# Insole_ver1_chi.net
KiCad netlist of a schematic drawn in Altium Designer
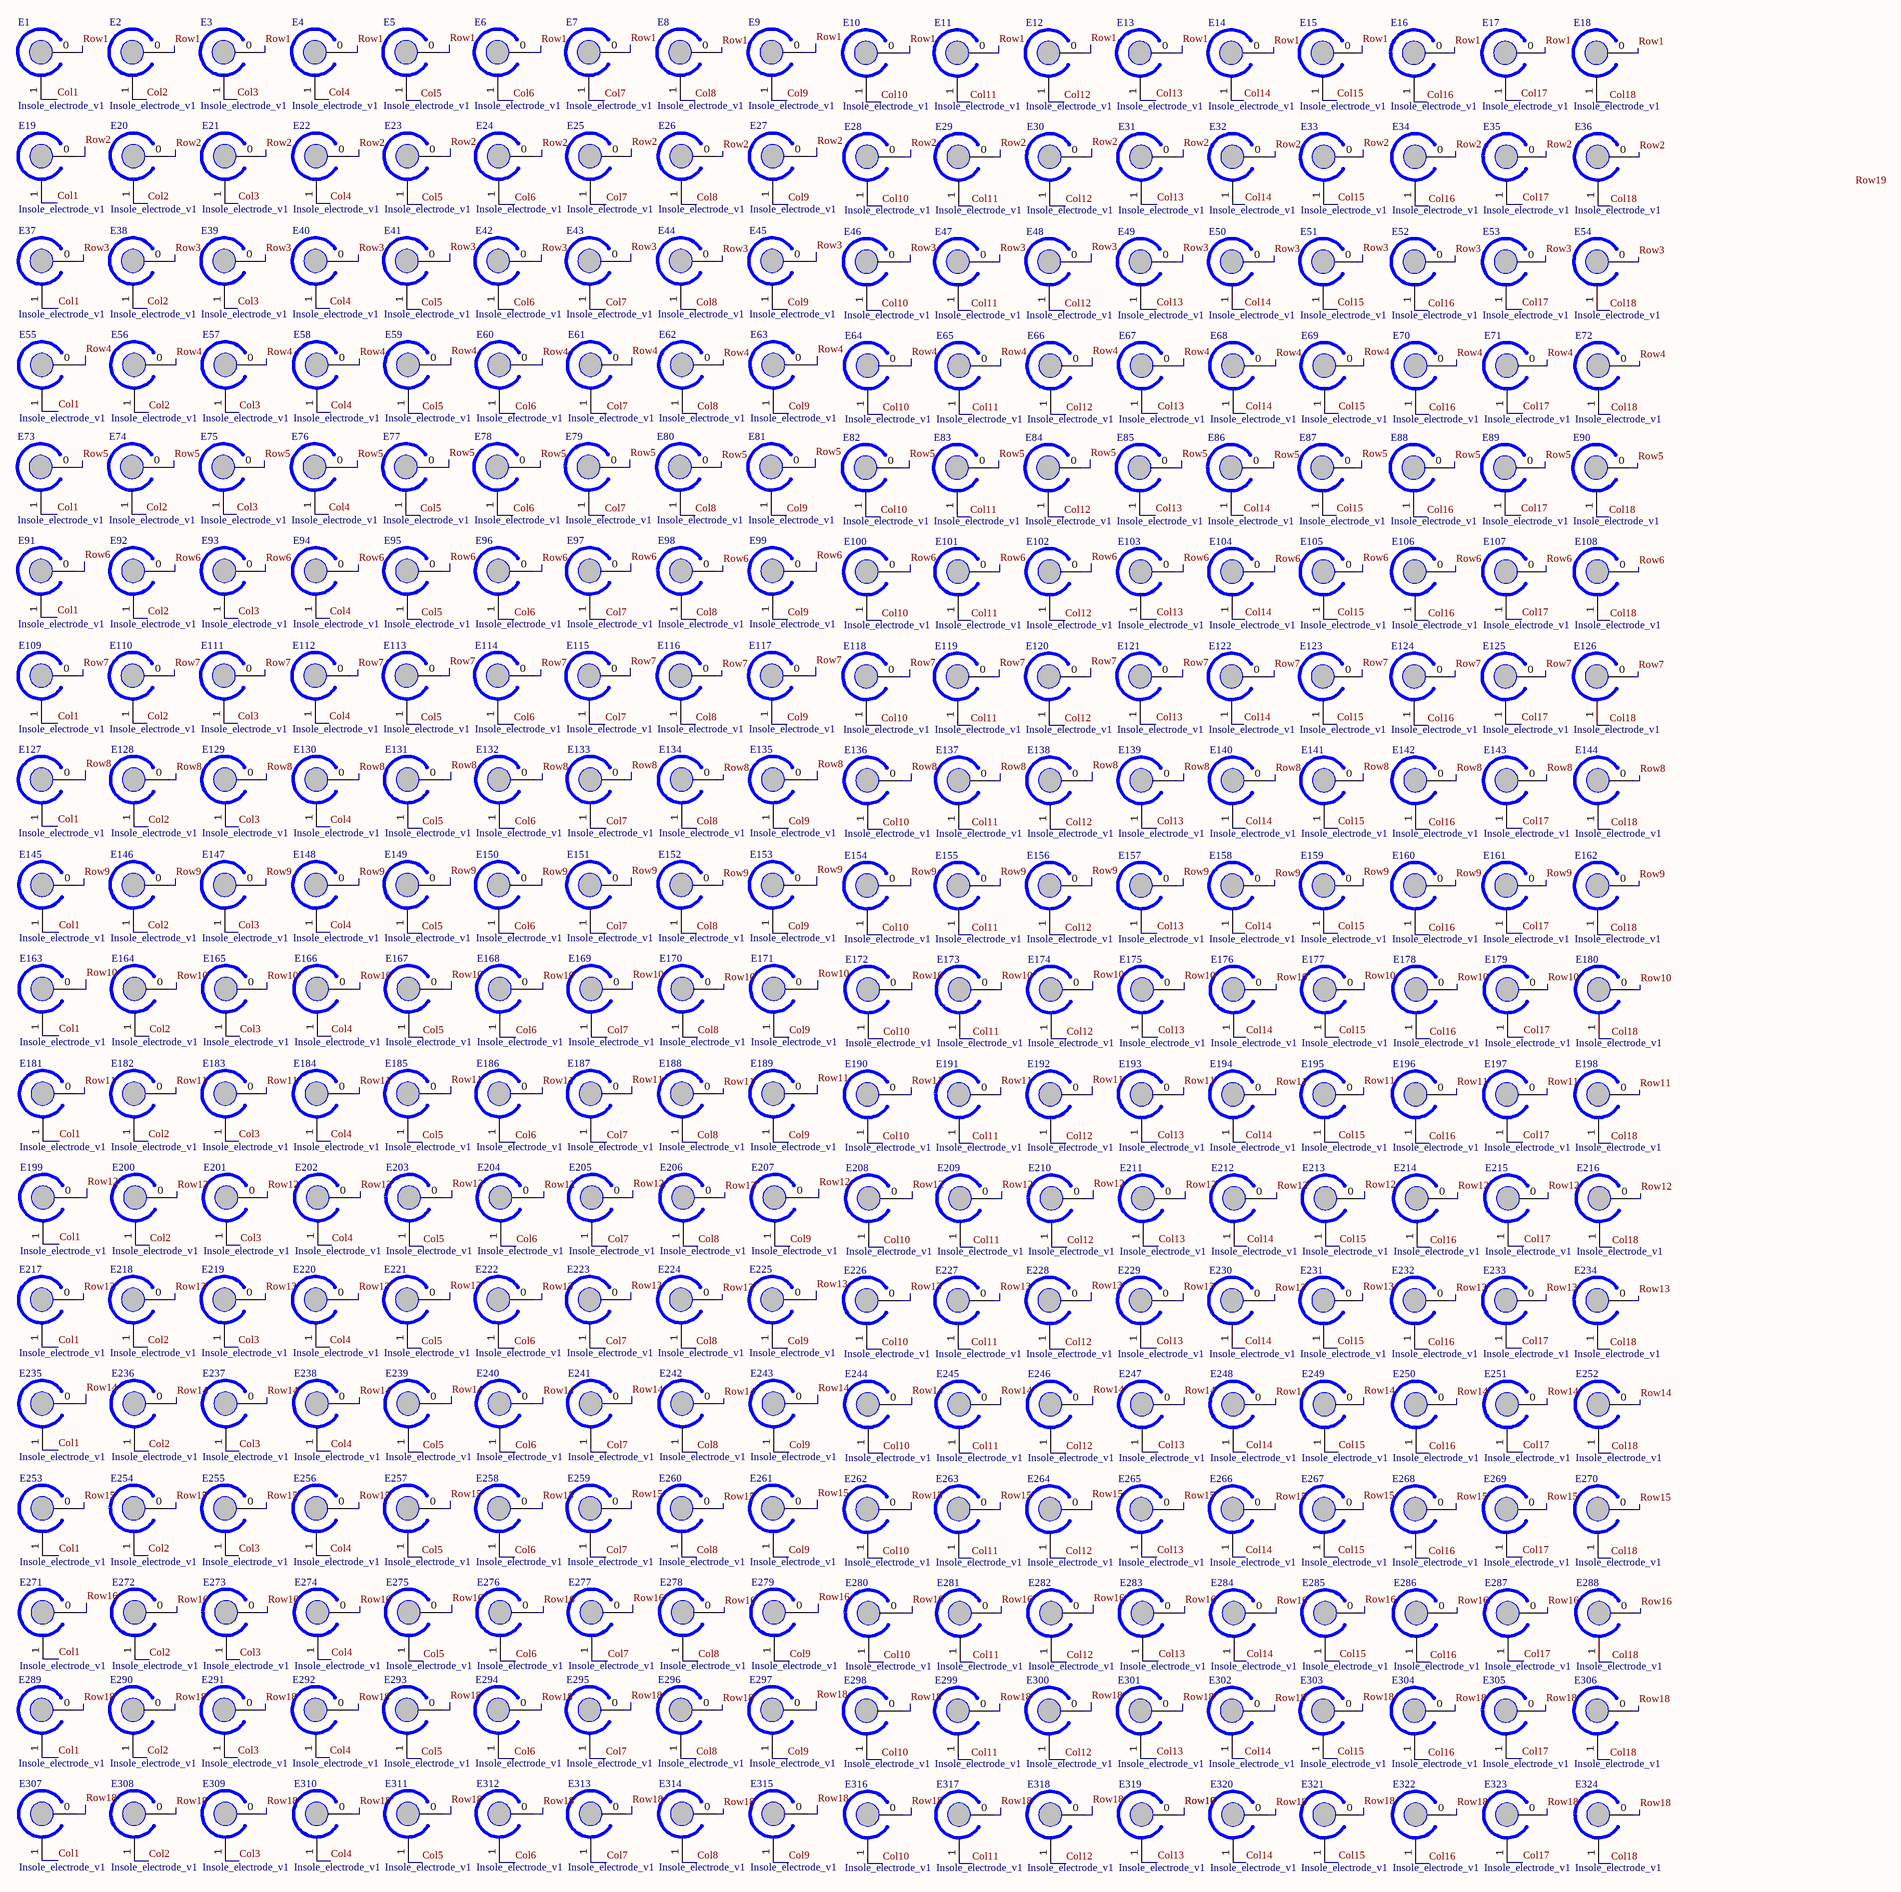
[diagram p0: Insole_ver1_chi.SchDoc]

(export (version "E")
  (design (tool "Eeschema 10.0.6"))
  (components
    (comp (ref "E1")
      (value "Insole_electrode_v1")
      (footprint "insole_electrode_v1")
      (libsource (lib "UCL") (part "Insole_electrode_v1"))
    )
    (comp (ref "E2")
      (value "Insole_electrode_v1")
      (footprint "insole_electrode_v1")
      (libsource (lib "UCL") (part "Insole_electrode_v1"))
    )
    (comp (ref "E3")
      (value "Insole_electrode_v1")
      (footprint "insole_electrode_v1")
      (libsource (lib "UCL") (part "Insole_electrode_v1"))
    )
    (comp (ref "E4")
      (value "Insole_electrode_v1")
      (footprint "insole_electrode_v1")
      (libsource (lib "UCL") (part "Insole_electrode_v1"))
    )
    (comp (ref "E5")
      (value "Insole_electrode_v1")
      (footprint "insole_electrode_v1")
      (libsource (lib "UCL") (part "Insole_electrode_v1"))
    )
    (comp (ref "E6")
      (value "Insole_electrode_v1")
      (footprint "insole_electrode_v1")
      (libsource (lib "UCL") (part "Insole_electrode_v1"))
    )
    (comp (ref "E7")
      (value "Insole_electrode_v1")
      (footprint "insole_electrode_v1")
      (libsource (lib "UCL") (part "Insole_electrode_v1"))
    )
    (comp (ref "E8")
      (value "Insole_electrode_v1")
      (footprint "insole_electrode_v1")
      (libsource (lib "UCL") (part "Insole_electrode_v1"))
    )
    (comp (ref "E9")
      (value "Insole_electrode_v1")
      (footprint "insole_electrode_v1")
      (libsource (lib "UCL") (part "Insole_electrode_v1"))
    )
    (comp (ref "E10")
      (value "Insole_electrode_v1")
      (footprint "insole_electrode_v1")
      (libsource (lib "UCL") (part "Insole_electrode_v1"))
    )
    (comp (ref "E11")
      (value "Insole_electrode_v1")
      (footprint "insole_electrode_v1")
      (libsource (lib "UCL") (part "Insole_electrode_v1"))
    )
    (comp (ref "E12")
      (value "Insole_electrode_v1")
      (footprint "insole_electrode_v1")
      (libsource (lib "UCL") (part "Insole_electrode_v1"))
    )
    (comp (ref "E13")
      (value "Insole_electrode_v1")
      (footprint "insole_electrode_v1")
      (libsource (lib "UCL") (part "Insole_electrode_v1"))
    )
    (comp (ref "E14")
      (value "Insole_electrode_v1")
      (footprint "insole_electrode_v1")
      (libsource (lib "UCL") (part "Insole_electrode_v1"))
    )
    (comp (ref "E15")
      (value "Insole_electrode_v1")
      (footprint "insole_electrode_v1")
      (libsource (lib "UCL") (part "Insole_electrode_v1"))
    )
    (comp (ref "E16")
      (value "Insole_electrode_v1")
      (footprint "insole_electrode_v1")
      (libsource (lib "UCL") (part "Insole_electrode_v1"))
    )
    (comp (ref "E17")
      (value "Insole_electrode_v1")
      (footprint "insole_electrode_v1")
      (libsource (lib "UCL") (part "Insole_electrode_v1"))
    )
    (comp (ref "E18")
      (value "Insole_electrode_v1")
      (footprint "insole_electrode_v1")
      (libsource (lib "UCL") (part "Insole_electrode_v1"))
    )
    (comp (ref "E19")
      (value "Insole_electrode_v1")
      (footprint "insole_electrode_v1")
      (libsource (lib "UCL") (part "Insole_electrode_v1"))
    )
    (comp (ref "E20")
      (value "Insole_electrode_v1")
      (footprint "insole_electrode_v1")
      (libsource (lib "UCL") (part "Insole_electrode_v1"))
    )
    (comp (ref "E21")
      (value "Insole_electrode_v1")
      (footprint "insole_electrode_v1")
      (libsource (lib "UCL") (part "Insole_electrode_v1"))
    )
    (comp (ref "E22")
      (value "Insole_electrode_v1")
      (footprint "insole_electrode_v1")
      (libsource (lib "UCL") (part "Insole_electrode_v1"))
    )
    (comp (ref "E23")
      (value "Insole_electrode_v1")
      (footprint "insole_electrode_v1")
      (libsource (lib "UCL") (part "Insole_electrode_v1"))
    )
    (comp (ref "E24")
      (value "Insole_electrode_v1")
      (footprint "insole_electrode_v1")
      (libsource (lib "UCL") (part "Insole_electrode_v1"))
    )
    (comp (ref "E25")
      (value "Insole_electrode_v1")
      (footprint "insole_electrode_v1")
      (libsource (lib "UCL") (part "Insole_electrode_v1"))
    )
    (comp (ref "E26")
      (value "Insole_electrode_v1")
      (footprint "insole_electrode_v1")
      (libsource (lib "UCL") (part "Insole_electrode_v1"))
    )
    (comp (ref "E27")
      (value "Insole_electrode_v1")
      (footprint "insole_electrode_v1")
      (libsource (lib "UCL") (part "Insole_electrode_v1"))
    )
    (comp (ref "E28")
      (value "Insole_electrode_v1")
      (footprint "insole_electrode_v1")
      (libsource (lib "UCL") (part "Insole_electrode_v1"))
    )
    (comp (ref "E29")
      (value "Insole_electrode_v1")
      (footprint "insole_electrode_v1")
      (libsource (lib "UCL") (part "Insole_electrode_v1"))
    )
    (comp (ref "E30")
      (value "Insole_electrode_v1")
      (footprint "insole_electrode_v1")
      (libsource (lib "UCL") (part "Insole_electrode_v1"))
    )
    (comp (ref "E31")
      (value "Insole_electrode_v1")
      (footprint "insole_electrode_v1")
      (libsource (lib "UCL") (part "Insole_electrode_v1"))
    )
    (comp (ref "E32")
      (value "Insole_electrode_v1")
      (footprint "insole_electrode_v1")
      (libsource (lib "UCL") (part "Insole_electrode_v1"))
    )
    (comp (ref "E33")
      (value "Insole_electrode_v1")
      (footprint "insole_electrode_v1")
      (libsource (lib "UCL") (part "Insole_electrode_v1"))
    )
    (comp (ref "E34")
      (value "Insole_electrode_v1")
      (footprint "insole_electrode_v1")
      (libsource (lib "UCL") (part "Insole_electrode_v1"))
    )
    (comp (ref "E35")
      (value "Insole_electrode_v1")
      (footprint "insole_electrode_v1")
      (libsource (lib "UCL") (part "Insole_electrode_v1"))
    )
    (comp (ref "E36")
      (value "Insole_electrode_v1")
      (footprint "insole_electrode_v1")
      (libsource (lib "UCL") (part "Insole_electrode_v1"))
    )
    (comp (ref "E37")
      (value "Insole_electrode_v1")
      (footprint "insole_electrode_v1")
      (libsource (lib "UCL") (part "Insole_electrode_v1"))
    )
    (comp (ref "E38")
      (value "Insole_electrode_v1")
      (footprint "insole_electrode_v1")
      (libsource (lib "UCL") (part "Insole_electrode_v1"))
    )
    (comp (ref "E39")
      (value "Insole_electrode_v1")
      (footprint "insole_electrode_v1")
      (libsource (lib "UCL") (part "Insole_electrode_v1"))
    )
    (comp (ref "E40")
      (value "Insole_electrode_v1")
      (footprint "insole_electrode_v1")
      (libsource (lib "UCL") (part "Insole_electrode_v1"))
    )
    (comp (ref "E41")
      (value "Insole_electrode_v1")
      (footprint "insole_electrode_v1")
      (libsource (lib "UCL") (part "Insole_electrode_v1"))
    )
    (comp (ref "E42")
      (value "Insole_electrode_v1")
      (footprint "insole_electrode_v1")
      (libsource (lib "UCL") (part "Insole_electrode_v1"))
    )
    (comp (ref "E43")
      (value "Insole_electrode_v1")
      (footprint "insole_electrode_v1")
      (libsource (lib "UCL") (part "Insole_electrode_v1"))
    )
    (comp (ref "E44")
      (value "Insole_electrode_v1")
      (footprint "insole_electrode_v1")
      (libsource (lib "UCL") (part "Insole_electrode_v1"))
    )
    (comp (ref "E45")
      (value "Insole_electrode_v1")
      (footprint "insole_electrode_v1")
      (libsource (lib "UCL") (part "Insole_electrode_v1"))
    )
    (comp (ref "E46")
      (value "Insole_electrode_v1")
      (footprint "insole_electrode_v1")
      (libsource (lib "UCL") (part "Insole_electrode_v1"))
    )
    (comp (ref "E47")
      (value "Insole_electrode_v1")
      (footprint "insole_electrode_v1")
      (libsource (lib "UCL") (part "Insole_electrode_v1"))
    )
    (comp (ref "E48")
      (value "Insole_electrode_v1")
      (footprint "insole_electrode_v1")
      (libsource (lib "UCL") (part "Insole_electrode_v1"))
    )
    (comp (ref "E49")
      (value "Insole_electrode_v1")
      (footprint "insole_electrode_v1")
      (libsource (lib "UCL") (part "Insole_electrode_v1"))
    )
    (comp (ref "E50")
      (value "Insole_electrode_v1")
      (footprint "insole_electrode_v1")
      (libsource (lib "UCL") (part "Insole_electrode_v1"))
    )
    (comp (ref "E51")
      (value "Insole_electrode_v1")
      (footprint "insole_electrode_v1")
      (libsource (lib "UCL") (part "Insole_electrode_v1"))
    )
    (comp (ref "E52")
      (value "Insole_electrode_v1")
      (footprint "insole_electrode_v1")
      (libsource (lib "UCL") (part "Insole_electrode_v1"))
    )
    (comp (ref "E53")
      (value "Insole_electrode_v1")
      (footprint "insole_electrode_v1")
      (libsource (lib "UCL") (part "Insole_electrode_v1"))
    )
    (comp (ref "E54")
      (value "Insole_electrode_v1")
      (footprint "insole_electrode_v1")
      (libsource (lib "UCL") (part "Insole_electrode_v1"))
    )
    (comp (ref "E55")
      (value "Insole_electrode_v1")
      (footprint "insole_electrode_v1")
      (libsource (lib "UCL") (part "Insole_electrode_v1"))
    )
    (comp (ref "E56")
      (value "Insole_electrode_v1")
      (footprint "insole_electrode_v1")
      (libsource (lib "UCL") (part "Insole_electrode_v1"))
    )
    (comp (ref "E57")
      (value "Insole_electrode_v1")
      (footprint "insole_electrode_v1")
      (libsource (lib "UCL") (part "Insole_electrode_v1"))
    )
    (comp (ref "E58")
      (value "Insole_electrode_v1")
      (footprint "insole_electrode_v1")
      (libsource (lib "UCL") (part "Insole_electrode_v1"))
    )
    (comp (ref "E59")
      (value "Insole_electrode_v1")
      (footprint "insole_electrode_v1")
      (libsource (lib "UCL") (part "Insole_electrode_v1"))
    )
    (comp (ref "E60")
      (value "Insole_electrode_v1")
      (footprint "insole_electrode_v1")
      (libsource (lib "UCL") (part "Insole_electrode_v1"))
    )
    (comp (ref "E61")
      (value "Insole_electrode_v1")
      (footprint "insole_electrode_v1")
      (libsource (lib "UCL") (part "Insole_electrode_v1"))
    )
    (comp (ref "E62")
      (value "Insole_electrode_v1")
      (footprint "insole_electrode_v1")
      (libsource (lib "UCL") (part "Insole_electrode_v1"))
    )
    (comp (ref "E63")
      (value "Insole_electrode_v1")
      (footprint "insole_electrode_v1")
      (libsource (lib "UCL") (part "Insole_electrode_v1"))
    )
    (comp (ref "E64")
      (value "Insole_electrode_v1")
      (footprint "insole_electrode_v1")
      (libsource (lib "UCL") (part "Insole_electrode_v1"))
    )
    (comp (ref "E65")
      (value "Insole_electrode_v1")
      (footprint "insole_electrode_v1")
      (libsource (lib "UCL") (part "Insole_electrode_v1"))
    )
    (comp (ref "E66")
      (value "Insole_electrode_v1")
      (footprint "insole_electrode_v1")
      (libsource (lib "UCL") (part "Insole_electrode_v1"))
    )
    (comp (ref "E67")
      (value "Insole_electrode_v1")
      (footprint "insole_electrode_v1")
      (libsource (lib "UCL") (part "Insole_electrode_v1"))
    )
    (comp (ref "E68")
      (value "Insole_electrode_v1")
      (footprint "insole_electrode_v1")
      (libsource (lib "UCL") (part "Insole_electrode_v1"))
    )
    (comp (ref "E69")
      (value "Insole_electrode_v1")
      (footprint "insole_electrode_v1")
      (libsource (lib "UCL") (part "Insole_electrode_v1"))
    )
    (comp (ref "E70")
      (value "Insole_electrode_v1")
      (footprint "insole_electrode_v1")
      (libsource (lib "UCL") (part "Insole_electrode_v1"))
    )
    (comp (ref "E71")
      (value "Insole_electrode_v1")
      (footprint "insole_electrode_v1")
      (libsource (lib "UCL") (part "Insole_electrode_v1"))
    )
    (comp (ref "E72")
      (value "Insole_electrode_v1")
      (footprint "insole_electrode_v1")
      (libsource (lib "UCL") (part "Insole_electrode_v1"))
    )
    (comp (ref "E73")
      (value "Insole_electrode_v1")
      (footprint "insole_electrode_v1")
      (libsource (lib "UCL") (part "Insole_electrode_v1"))
    )
    (comp (ref "E74")
      (value "Insole_electrode_v1")
      (footprint "insole_electrode_v1")
      (libsource (lib "UCL") (part "Insole_electrode_v1"))
    )
    (comp (ref "E75")
      (value "Insole_electrode_v1")
      (footprint "insole_electrode_v1")
      (libsource (lib "UCL") (part "Insole_electrode_v1"))
    )
    (comp (ref "E76")
      (value "Insole_electrode_v1")
      (footprint "insole_electrode_v1")
      (libsource (lib "UCL") (part "Insole_electrode_v1"))
    )
    (comp (ref "E77")
      (value "Insole_electrode_v1")
      (footprint "insole_electrode_v1")
      (libsource (lib "UCL") (part "Insole_electrode_v1"))
    )
    (comp (ref "E78")
      (value "Insole_electrode_v1")
      (footprint "insole_electrode_v1")
      (libsource (lib "UCL") (part "Insole_electrode_v1"))
    )
    (comp (ref "E79")
      (value "Insole_electrode_v1")
      (footprint "insole_electrode_v1")
      (libsource (lib "UCL") (part "Insole_electrode_v1"))
    )
    (comp (ref "E80")
      (value "Insole_electrode_v1")
      (footprint "insole_electrode_v1")
      (libsource (lib "UCL") (part "Insole_electrode_v1"))
    )
    (comp (ref "E81")
      (value "Insole_electrode_v1")
      (footprint "insole_electrode_v1")
      (libsource (lib "UCL") (part "Insole_electrode_v1"))
    )
    (comp (ref "E82")
      (value "Insole_electrode_v1")
      (footprint "insole_electrode_v1")
      (libsource (lib "UCL") (part "Insole_electrode_v1"))
    )
    (comp (ref "E83")
      (value "Insole_electrode_v1")
      (footprint "insole_electrode_v1")
      (libsource (lib "UCL") (part "Insole_electrode_v1"))
    )
    (comp (ref "E84")
      (value "Insole_electrode_v1")
      (footprint "insole_electrode_v1")
      (libsource (lib "UCL") (part "Insole_electrode_v1"))
    )
    (comp (ref "E85")
      (value "Insole_electrode_v1")
      (footprint "insole_electrode_v1")
      (libsource (lib "UCL") (part "Insole_electrode_v1"))
    )
    (comp (ref "E86")
      (value "Insole_electrode_v1")
      (footprint "insole_electrode_v1")
      (libsource (lib "UCL") (part "Insole_electrode_v1"))
    )
    (comp (ref "E87")
      (value "Insole_electrode_v1")
      (footprint "insole_electrode_v1")
      (libsource (lib "UCL") (part "Insole_electrode_v1"))
    )
    (comp (ref "E88")
      (value "Insole_electrode_v1")
      (footprint "insole_electrode_v1")
      (libsource (lib "UCL") (part "Insole_electrode_v1"))
    )
    (comp (ref "E89")
      (value "Insole_electrode_v1")
      (footprint "insole_electrode_v1")
      (libsource (lib "UCL") (part "Insole_electrode_v1"))
    )
    (comp (ref "E90")
      (value "Insole_electrode_v1")
      (footprint "insole_electrode_v1")
      (libsource (lib "UCL") (part "Insole_electrode_v1"))
    )
    (comp (ref "E91")
      (value "Insole_electrode_v1")
      (footprint "insole_electrode_v1")
      (libsource (lib "UCL") (part "Insole_electrode_v1"))
    )
    (comp (ref "E92")
      (value "Insole_electrode_v1")
      (footprint "insole_electrode_v1")
      (libsource (lib "UCL") (part "Insole_electrode_v1"))
    )
    (comp (ref "E93")
      (value "Insole_electrode_v1")
      (footprint "insole_electrode_v1")
      (libsource (lib "UCL") (part "Insole_electrode_v1"))
    )
    (comp (ref "E94")
      (value "Insole_electrode_v1")
      (footprint "insole_electrode_v1")
      (libsource (lib "UCL") (part "Insole_electrode_v1"))
    )
    (comp (ref "E95")
      (value "Insole_electrode_v1")
      (footprint "insole_electrode_v1")
      (libsource (lib "UCL") (part "Insole_electrode_v1"))
    )
    (comp (ref "E96")
      (value "Insole_electrode_v1")
      (footprint "insole_electrode_v1")
      (libsource (lib "UCL") (part "Insole_electrode_v1"))
    )
    (comp (ref "E97")
      (value "Insole_electrode_v1")
      (footprint "insole_electrode_v1")
      (libsource (lib "UCL") (part "Insole_electrode_v1"))
    )
    (comp (ref "E98")
      (value "Insole_electrode_v1")
      (footprint "insole_electrode_v1")
      (libsource (lib "UCL") (part "Insole_electrode_v1"))
    )
    (comp (ref "E99")
      (value "Insole_electrode_v1")
      (footprint "insole_electrode_v1")
      (libsource (lib "UCL") (part "Insole_electrode_v1"))
    )
    (comp (ref "E100")
      (value "Insole_electrode_v1")
      (footprint "insole_electrode_v1")
      (libsource (lib "UCL") (part "Insole_electrode_v1"))
    )
    (comp (ref "E101")
      (value "Insole_electrode_v1")
      (footprint "insole_electrode_v1")
      (libsource (lib "UCL") (part "Insole_electrode_v1"))
    )
    (comp (ref "E102")
      (value "Insole_electrode_v1")
      (footprint "insole_electrode_v1")
      (libsource (lib "UCL") (part "Insole_electrode_v1"))
    )
    (comp (ref "E103")
      (value "Insole_electrode_v1")
      (footprint "insole_electrode_v1")
      (libsource (lib "UCL") (part "Insole_electrode_v1"))
    )
    (comp (ref "E104")
      (value "Insole_electrode_v1")
      (footprint "insole_electrode_v1")
      (libsource (lib "UCL") (part "Insole_electrode_v1"))
    )
    (comp (ref "E105")
      (value "Insole_electrode_v1")
      (footprint "insole_electrode_v1")
      (libsource (lib "UCL") (part "Insole_electrode_v1"))
    )
    (comp (ref "E106")
      (value "Insole_electrode_v1")
      (footprint "insole_electrode_v1")
      (libsource (lib "UCL") (part "Insole_electrode_v1"))
    )
    (comp (ref "E107")
      (value "Insole_electrode_v1")
      (footprint "insole_electrode_v1")
      (libsource (lib "UCL") (part "Insole_electrode_v1"))
    )
    (comp (ref "E108")
      (value "Insole_electrode_v1")
      (footprint "insole_electrode_v1")
      (libsource (lib "UCL") (part "Insole_electrode_v1"))
    )
    (comp (ref "E109")
      (value "Insole_electrode_v1")
      (footprint "insole_electrode_v1")
      (libsource (lib "UCL") (part "Insole_electrode_v1"))
    )
    (comp (ref "E110")
      (value "Insole_electrode_v1")
      (footprint "insole_electrode_v1")
      (libsource (lib "UCL") (part "Insole_electrode_v1"))
    )
    (comp (ref "E111")
      (value "Insole_electrode_v1")
      (footprint "insole_electrode_v1")
      (libsource (lib "UCL") (part "Insole_electrode_v1"))
    )
    (comp (ref "E112")
      (value "Insole_electrode_v1")
      (footprint "insole_electrode_v1")
      (libsource (lib "UCL") (part "Insole_electrode_v1"))
    )
    (comp (ref "E113")
      (value "Insole_electrode_v1")
      (footprint "insole_electrode_v1")
      (libsource (lib "UCL") (part "Insole_electrode_v1"))
    )
    (comp (ref "E114")
      (value "Insole_electrode_v1")
      (footprint "insole_electrode_v1")
      (libsource (lib "UCL") (part "Insole_electrode_v1"))
    )
    (comp (ref "E115")
      (value "Insole_electrode_v1")
      (footprint "insole_electrode_v1")
      (libsource (lib "UCL") (part "Insole_electrode_v1"))
    )
    (comp (ref "E116")
      (value "Insole_electrode_v1")
      (footprint "insole_electrode_v1")
      (libsource (lib "UCL") (part "Insole_electrode_v1"))
    )
    (comp (ref "E117")
      (value "Insole_electrode_v1")
      (footprint "insole_electrode_v1")
      (libsource (lib "UCL") (part "Insole_electrode_v1"))
    )
    (comp (ref "E118")
      (value "Insole_electrode_v1")
      (footprint "insole_electrode_v1")
      (libsource (lib "UCL") (part "Insole_electrode_v1"))
    )
    (comp (ref "E119")
      (value "Insole_electrode_v1")
      (footprint "insole_electrode_v1")
      (libsource (lib "UCL") (part "Insole_electrode_v1"))
    )
    (comp (ref "E120")
      (value "Insole_electrode_v1")
      (footprint "insole_electrode_v1")
      (libsource (lib "UCL") (part "Insole_electrode_v1"))
    )
    (comp (ref "E121")
      (value "Insole_electrode_v1")
      (footprint "insole_electrode_v1")
      (libsource (lib "UCL") (part "Insole_electrode_v1"))
    )
    (comp (ref "E122")
      (value "Insole_electrode_v1")
      (footprint "insole_electrode_v1")
      (libsource (lib "UCL") (part "Insole_electrode_v1"))
    )
    (comp (ref "E123")
      (value "Insole_electrode_v1")
      (footprint "insole_electrode_v1")
      (libsource (lib "UCL") (part "Insole_electrode_v1"))
    )
    (comp (ref "E124")
      (value "Insole_electrode_v1")
      (footprint "insole_electrode_v1")
      (libsource (lib "UCL") (part "Insole_electrode_v1"))
    )
    (comp (ref "E125")
      (value "Insole_electrode_v1")
      (footprint "insole_electrode_v1")
      (libsource (lib "UCL") (part "Insole_electrode_v1"))
    )
    (comp (ref "E126")
      (value "Insole_electrode_v1")
      (footprint "insole_electrode_v1")
      (libsource (lib "UCL") (part "Insole_electrode_v1"))
    )
    (comp (ref "E127")
      (value "Insole_electrode_v1")
      (footprint "insole_electrode_v1")
      (libsource (lib "UCL") (part "Insole_electrode_v1"))
    )
    (comp (ref "E128")
      (value "Insole_electrode_v1")
      (footprint "insole_electrode_v1")
      (libsource (lib "UCL") (part "Insole_electrode_v1"))
    )
    (comp (ref "E129")
      (value "Insole_electrode_v1")
      (footprint "insole_electrode_v1")
      (libsource (lib "UCL") (part "Insole_electrode_v1"))
    )
    (comp (ref "E130")
      (value "Insole_electrode_v1")
      (footprint "insole_electrode_v1")
      (libsource (lib "UCL") (part "Insole_electrode_v1"))
    )
    (comp (ref "E131")
      (value "Insole_electrode_v1")
      (footprint "insole_electrode_v1")
      (libsource (lib "UCL") (part "Insole_electrode_v1"))
    )
    (comp (ref "E132")
      (value "Insole_electrode_v1")
      (footprint "insole_electrode_v1")
      (libsource (lib "UCL") (part "Insole_electrode_v1"))
    )
    (comp (ref "E133")
      (value "Insole_electrode_v1")
      (footprint "insole_electrode_v1")
      (libsource (lib "UCL") (part "Insole_electrode_v1"))
    )
    (comp (ref "E134")
      (value "Insole_electrode_v1")
      (footprint "insole_electrode_v1")
      (libsource (lib "UCL") (part "Insole_electrode_v1"))
    )
    (comp (ref "E135")
      (value "Insole_electrode_v1")
      (footprint "insole_electrode_v1")
      (libsource (lib "UCL") (part "Insole_electrode_v1"))
    )
    (comp (ref "E136")
      (value "Insole_electrode_v1")
      (footprint "insole_electrode_v1")
      (libsource (lib "UCL") (part "Insole_electrode_v1"))
    )
    (comp (ref "E137")
      (value "Insole_electrode_v1")
      (footprint "insole_electrode_v1")
      (libsource (lib "UCL") (part "Insole_electrode_v1"))
    )
    (comp (ref "E138")
      (value "Insole_electrode_v1")
      (footprint "insole_electrode_v1")
      (libsource (lib "UCL") (part "Insole_electrode_v1"))
    )
    (comp (ref "E139")
      (value "Insole_electrode_v1")
      (footprint "insole_electrode_v1")
      (libsource (lib "UCL") (part "Insole_electrode_v1"))
    )
    (comp (ref "E140")
      (value "Insole_electrode_v1")
      (footprint "insole_electrode_v1")
      (libsource (lib "UCL") (part "Insole_electrode_v1"))
    )
    (comp (ref "E141")
      (value "Insole_electrode_v1")
      (footprint "insole_electrode_v1")
      (libsource (lib "UCL") (part "Insole_electrode_v1"))
    )
    (comp (ref "E142")
      (value "Insole_electrode_v1")
      (footprint "insole_electrode_v1")
      (libsource (lib "UCL") (part "Insole_electrode_v1"))
    )
    (comp (ref "E143")
      (value "Insole_electrode_v1")
      (footprint "insole_electrode_v1")
      (libsource (lib "UCL") (part "Insole_electrode_v1"))
    )
    (comp (ref "E144")
      (value "Insole_electrode_v1")
      (footprint "insole_electrode_v1")
      (libsource (lib "UCL") (part "Insole_electrode_v1"))
    )
    (comp (ref "E145")
      (value "Insole_electrode_v1")
      (footprint "insole_electrode_v1")
      (libsource (lib "UCL") (part "Insole_electrode_v1"))
    )
    (comp (ref "E146")
      (value "Insole_electrode_v1")
      (footprint "insole_electrode_v1")
      (libsource (lib "UCL") (part "Insole_electrode_v1"))
    )
    (comp (ref "E147")
      (value "Insole_electrode_v1")
      (footprint "insole_electrode_v1")
      (libsource (lib "UCL") (part "Insole_electrode_v1"))
    )
    (comp (ref "E148")
      (value "Insole_electrode_v1")
      (footprint "insole_electrode_v1")
      (libsource (lib "UCL") (part "Insole_electrode_v1"))
    )
    (comp (ref "E149")
      (value "Insole_electrode_v1")
      (footprint "insole_electrode_v1")
      (libsource (lib "UCL") (part "Insole_electrode_v1"))
    )
    (comp (ref "E150")
      (value "Insole_electrode_v1")
      (footprint "insole_electrode_v1")
      (libsource (lib "UCL") (part "Insole_electrode_v1"))
    )
    (comp (ref "E151")
      (value "Insole_electrode_v1")
      (footprint "insole_electrode_v1")
      (libsource (lib "UCL") (part "Insole_electrode_v1"))
    )
    (comp (ref "E152")
      (value "Insole_electrode_v1")
      (footprint "insole_electrode_v1")
      (libsource (lib "UCL") (part "Insole_electrode_v1"))
    )
    (comp (ref "E153")
      (value "Insole_electrode_v1")
      (footprint "insole_electrode_v1")
      (libsource (lib "UCL") (part "Insole_electrode_v1"))
    )
    (comp (ref "E154")
      (value "Insole_electrode_v1")
      (footprint "insole_electrode_v1")
      (libsource (lib "UCL") (part "Insole_electrode_v1"))
    )
    (comp (ref "E155")
      (value "Insole_electrode_v1")
      (footprint "insole_electrode_v1")
      (libsource (lib "UCL") (part "Insole_electrode_v1"))
    )
    (comp (ref "E156")
      (value "Insole_electrode_v1")
      (footprint "insole_electrode_v1")
      (libsource (lib "UCL") (part "Insole_electrode_v1"))
    )
    (comp (ref "E157")
      (value "Insole_electrode_v1")
      (footprint "insole_electrode_v1")
      (libsource (lib "UCL") (part "Insole_electrode_v1"))
    )
    (comp (ref "E158")
      (value "Insole_electrode_v1")
      (footprint "insole_electrode_v1")
      (libsource (lib "UCL") (part "Insole_electrode_v1"))
    )
    (comp (ref "E159")
      (value "Insole_electrode_v1")
      (footprint "insole_electrode_v1")
      (libsource (lib "UCL") (part "Insole_electrode_v1"))
    )
    (comp (ref "E160")
      (value "Insole_electrode_v1")
      (footprint "insole_electrode_v1")
      (libsource (lib "UCL") (part "Insole_electrode_v1"))
    )
    (comp (ref "E161")
      (value "Insole_electrode_v1")
      (footprint "insole_electrode_v1")
      (libsource (lib "UCL") (part "Insole_electrode_v1"))
    )
    (comp (ref "E162")
      (value "Insole_electrode_v1")
      (footprint "insole_electrode_v1")
      (libsource (lib "UCL") (part "Insole_electrode_v1"))
    )
    (comp (ref "E163")
      (value "Insole_electrode_v1")
      (footprint "insole_electrode_v1")
      (libsource (lib "UCL") (part "Insole_electrode_v1"))
    )
    (comp (ref "E164")
      (value "Insole_electrode_v1")
      (footprint "insole_electrode_v1")
      (libsource (lib "UCL") (part "Insole_electrode_v1"))
    )
    (comp (ref "E165")
      (value "Insole_electrode_v1")
      (footprint "insole_electrode_v1")
      (libsource (lib "UCL") (part "Insole_electrode_v1"))
    )
    (comp (ref "E166")
      (value "Insole_electrode_v1")
      (footprint "insole_electrode_v1")
      (libsource (lib "UCL") (part "Insole_electrode_v1"))
    )
    (comp (ref "E167")
      (value "Insole_electrode_v1")
      (footprint "insole_electrode_v1")
      (libsource (lib "UCL") (part "Insole_electrode_v1"))
    )
    (comp (ref "E168")
      (value "Insole_electrode_v1")
      (footprint "insole_electrode_v1")
      (libsource (lib "UCL") (part "Insole_electrode_v1"))
    )
    (comp (ref "E169")
      (value "Insole_electrode_v1")
      (footprint "insole_electrode_v1")
      (libsource (lib "UCL") (part "Insole_electrode_v1"))
    )
    (comp (ref "E170")
      (value "Insole_electrode_v1")
      (footprint "insole_electrode_v1")
      (libsource (lib "UCL") (part "Insole_electrode_v1"))
    )
    (comp (ref "E171")
      (value "Insole_electrode_v1")
      (footprint "insole_electrode_v1")
      (libsource (lib "UCL") (part "Insole_electrode_v1"))
    )
    (comp (ref "E172")
      (value "Insole_electrode_v1")
      (footprint "insole_electrode_v1")
      (libsource (lib "UCL") (part "Insole_electrode_v1"))
    )
    (comp (ref "E173")
      (value "Insole_electrode_v1")
      (footprint "insole_electrode_v1")
      (libsource (lib "UCL") (part "Insole_electrode_v1"))
    )
    (comp (ref "E174")
      (value "Insole_electrode_v1")
      (footprint "insole_electrode_v1")
      (libsource (lib "UCL") (part "Insole_electrode_v1"))
    )
    (comp (ref "E175")
      (value "Insole_electrode_v1")
      (footprint "insole_electrode_v1")
      (libsource (lib "UCL") (part "Insole_electrode_v1"))
    )
    (comp (ref "E176")
      (value "Insole_electrode_v1")
      (footprint "insole_electrode_v1")
      (libsource (lib "UCL") (part "Insole_electrode_v1"))
    )
    (comp (ref "E177")
      (value "Insole_electrode_v1")
      (footprint "insole_electrode_v1")
      (libsource (lib "UCL") (part "Insole_electrode_v1"))
    )
    (comp (ref "E178")
      (value "Insole_electrode_v1")
      (footprint "insole_electrode_v1")
      (libsource (lib "UCL") (part "Insole_electrode_v1"))
    )
    (comp (ref "E179")
      (value "Insole_electrode_v1")
      (footprint "insole_electrode_v1")
      (libsource (lib "UCL") (part "Insole_electrode_v1"))
    )
    (comp (ref "E180")
      (value "Insole_electrode_v1")
      (footprint "insole_electrode_v1")
      (libsource (lib "UCL") (part "Insole_electrode_v1"))
    )
    (comp (ref "E181")
      (value "Insole_electrode_v1")
      (footprint "insole_electrode_v1")
      (libsource (lib "UCL") (part "Insole_electrode_v1"))
    )
    (comp (ref "E182")
      (value "Insole_electrode_v1")
      (footprint "insole_electrode_v1")
      (libsource (lib "UCL") (part "Insole_electrode_v1"))
    )
    (comp (ref "E183")
      (value "Insole_electrode_v1")
      (footprint "insole_electrode_v1")
      (libsource (lib "UCL") (part "Insole_electrode_v1"))
    )
    (comp (ref "E184")
      (value "Insole_electrode_v1")
      (footprint "insole_electrode_v1")
      (libsource (lib "UCL") (part "Insole_electrode_v1"))
    )
    (comp (ref "E185")
      (value "Insole_electrode_v1")
      (footprint "insole_electrode_v1")
      (libsource (lib "UCL") (part "Insole_electrode_v1"))
    )
    (comp (ref "E186")
      (value "Insole_electrode_v1")
      (footprint "insole_electrode_v1")
      (libsource (lib "UCL") (part "Insole_electrode_v1"))
    )
    (comp (ref "E187")
      (value "Insole_electrode_v1")
      (footprint "insole_electrode_v1")
      (libsource (lib "UCL") (part "Insole_electrode_v1"))
    )
    (comp (ref "E188")
      (value "Insole_electrode_v1")
      (footprint "insole_electrode_v1")
      (libsource (lib "UCL") (part "Insole_electrode_v1"))
    )
    (comp (ref "E189")
      (value "Insole_electrode_v1")
      (footprint "insole_electrode_v1")
      (libsource (lib "UCL") (part "Insole_electrode_v1"))
    )
    (comp (ref "E190")
      (value "Insole_electrode_v1")
      (footprint "insole_electrode_v1")
      (libsource (lib "UCL") (part "Insole_electrode_v1"))
    )
    (comp (ref "E191")
      (value "Insole_electrode_v1")
      (footprint "insole_electrode_v1")
      (libsource (lib "UCL") (part "Insole_electrode_v1"))
    )
    (comp (ref "E192")
      (value "Insole_electrode_v1")
      (footprint "insole_electrode_v1")
      (libsource (lib "UCL") (part "Insole_electrode_v1"))
    )
    (comp (ref "E193")
      (value "Insole_electrode_v1")
      (footprint "insole_electrode_v1")
      (libsource (lib "UCL") (part "Insole_electrode_v1"))
    )
    (comp (ref "E194")
      (value "Insole_electrode_v1")
      (footprint "insole_electrode_v1")
      (libsource (lib "UCL") (part "Insole_electrode_v1"))
    )
    (comp (ref "E195")
      (value "Insole_electrode_v1")
      (footprint "insole_electrode_v1")
      (libsource (lib "UCL") (part "Insole_electrode_v1"))
    )
    (comp (ref "E196")
      (value "Insole_electrode_v1")
      (footprint "insole_electrode_v1")
      (libsource (lib "UCL") (part "Insole_electrode_v1"))
    )
    (comp (ref "E197")
      (value "Insole_electrode_v1")
      (footprint "insole_electrode_v1")
      (libsource (lib "UCL") (part "Insole_electrode_v1"))
    )
    (comp (ref "E198")
      (value "Insole_electrode_v1")
      (footprint "insole_electrode_v1")
      (libsource (lib "UCL") (part "Insole_electrode_v1"))
    )
    (comp (ref "E199")
      (value "Insole_electrode_v1")
      (footprint "insole_electrode_v1")
      (libsource (lib "UCL") (part "Insole_electrode_v1"))
    )
    (comp (ref "E200")
      (value "Insole_electrode_v1")
      (footprint "insole_electrode_v1")
      (libsource (lib "UCL") (part "Insole_electrode_v1"))
    )
    (comp (ref "E201")
      (value "Insole_electrode_v1")
      (footprint "insole_electrode_v1")
      (libsource (lib "UCL") (part "Insole_electrode_v1"))
    )
    (comp (ref "E202")
      (value "Insole_electrode_v1")
      (footprint "insole_electrode_v1")
      (libsource (lib "UCL") (part "Insole_electrode_v1"))
    )
    (comp (ref "E203")
      (value "Insole_electrode_v1")
      (footprint "insole_electrode_v1")
      (libsource (lib "UCL") (part "Insole_electrode_v1"))
    )
    (comp (ref "E204")
      (value "Insole_electrode_v1")
      (footprint "insole_electrode_v1")
      (libsource (lib "UCL") (part "Insole_electrode_v1"))
    )
    (comp (ref "E205")
      (value "Insole_electrode_v1")
      (footprint "insole_electrode_v1")
      (libsource (lib "UCL") (part "Insole_electrode_v1"))
    )
    (comp (ref "E206")
      (value "Insole_electrode_v1")
      (footprint "insole_electrode_v1")
      (libsource (lib "UCL") (part "Insole_electrode_v1"))
    )
    (comp (ref "E207")
      (value "Insole_electrode_v1")
      (footprint "insole_electrode_v1")
      (libsource (lib "UCL") (part "Insole_electrode_v1"))
    )
    (comp (ref "E208")
      (value "Insole_electrode_v1")
      (footprint "insole_electrode_v1")
      (libsource (lib "UCL") (part "Insole_electrode_v1"))
    )
    (comp (ref "E209")
      (value "Insole_electrode_v1")
      (footprint "insole_electrode_v1")
      (libsource (lib "UCL") (part "Insole_electrode_v1"))
    )
    (comp (ref "E210")
      (value "Insole_electrode_v1")
      (footprint "insole_electrode_v1")
      (libsource (lib "UCL") (part "Insole_electrode_v1"))
    )
    (comp (ref "E211")
      (value "Insole_electrode_v1")
      (footprint "insole_electrode_v1")
      (libsource (lib "UCL") (part "Insole_electrode_v1"))
    )
    (comp (ref "E212")
      (value "Insole_electrode_v1")
      (footprint "insole_electrode_v1")
      (libsource (lib "UCL") (part "Insole_electrode_v1"))
    )
    (comp (ref "E213")
      (value "Insole_electrode_v1")
      (footprint "insole_electrode_v1")
      (libsource (lib "UCL") (part "Insole_electrode_v1"))
    )
    (comp (ref "E214")
      (value "Insole_electrode_v1")
      (footprint "insole_electrode_v1")
      (libsource (lib "UCL") (part "Insole_electrode_v1"))
    )
    (comp (ref "E215")
      (value "Insole_electrode_v1")
      (footprint "insole_electrode_v1")
      (libsource (lib "UCL") (part "Insole_electrode_v1"))
    )
    (comp (ref "E216")
      (value "Insole_electrode_v1")
      (footprint "insole_electrode_v1")
      (libsource (lib "UCL") (part "Insole_electrode_v1"))
    )
    (comp (ref "E217")
      (value "Insole_electrode_v1")
      (footprint "insole_electrode_v1")
      (libsource (lib "UCL") (part "Insole_electrode_v1"))
    )
    (comp (ref "E218")
      (value "Insole_electrode_v1")
      (footprint "insole_electrode_v1")
      (libsource (lib "UCL") (part "Insole_electrode_v1"))
    )
    (comp (ref "E219")
      (value "Insole_electrode_v1")
      (footprint "insole_electrode_v1")
      (libsource (lib "UCL") (part "Insole_electrode_v1"))
    )
    (comp (ref "E220")
      (value "Insole_electrode_v1")
      (footprint "insole_electrode_v1")
      (libsource (lib "UCL") (part "Insole_electrode_v1"))
    )
    (comp (ref "E221")
      (value "Insole_electrode_v1")
      (footprint "insole_electrode_v1")
      (libsource (lib "UCL") (part "Insole_electrode_v1"))
    )
    (comp (ref "E222")
      (value "Insole_electrode_v1")
      (footprint "insole_electrode_v1")
      (libsource (lib "UCL") (part "Insole_electrode_v1"))
    )
    (comp (ref "E223")
      (value "Insole_electrode_v1")
      (footprint "insole_electrode_v1")
      (libsource (lib "UCL") (part "Insole_electrode_v1"))
    )
    (comp (ref "E224")
      (value "Insole_electrode_v1")
      (footprint "insole_electrode_v1")
      (libsource (lib "UCL") (part "Insole_electrode_v1"))
    )
    (comp (ref "E225")
      (value "Insole_electrode_v1")
      (footprint "insole_electrode_v1")
      (libsource (lib "UCL") (part "Insole_electrode_v1"))
    )
    (comp (ref "E226")
      (value "Insole_electrode_v1")
      (footprint "insole_electrode_v1")
      (libsource (lib "UCL") (part "Insole_electrode_v1"))
    )
    (comp (ref "E227")
      (value "Insole_electrode_v1")
      (footprint "insole_electrode_v1")
      (libsource (lib "UCL") (part "Insole_electrode_v1"))
    )
    (comp (ref "E228")
      (value "Insole_electrode_v1")
      (footprint "insole_electrode_v1")
      (libsource (lib "UCL") (part "Insole_electrode_v1"))
    )
    (comp (ref "E229")
      (value "Insole_electrode_v1")
      (footprint "insole_electrode_v1")
      (libsource (lib "UCL") (part "Insole_electrode_v1"))
    )
    (comp (ref "E230")
      (value "Insole_electrode_v1")
      (footprint "insole_electrode_v1")
      (libsource (lib "UCL") (part "Insole_electrode_v1"))
    )
    (comp (ref "E231")
      (value "Insole_electrode_v1")
      (footprint "insole_electrode_v1")
      (libsource (lib "UCL") (part "Insole_electrode_v1"))
    )
    (comp (ref "E232")
      (value "Insole_electrode_v1")
      (footprint "insole_electrode_v1")
      (libsource (lib "UCL") (part "Insole_electrode_v1"))
    )
    (comp (ref "E233")
      (value "Insole_electrode_v1")
      (footprint "insole_electrode_v1")
      (libsource (lib "UCL") (part "Insole_electrode_v1"))
    )
    (comp (ref "E234")
      (value "Insole_electrode_v1")
      (footprint "insole_electrode_v1")
      (libsource (lib "UCL") (part "Insole_electrode_v1"))
    )
    (comp (ref "E235")
      (value "Insole_electrode_v1")
      (footprint "insole_electrode_v1")
      (libsource (lib "UCL") (part "Insole_electrode_v1"))
    )
    (comp (ref "E236")
      (value "Insole_electrode_v1")
      (footprint "insole_electrode_v1")
      (libsource (lib "UCL") (part "Insole_electrode_v1"))
    )
    (comp (ref "E237")
      (value "Insole_electrode_v1")
      (footprint "insole_electrode_v1")
      (libsource (lib "UCL") (part "Insole_electrode_v1"))
    )
    (comp (ref "E238")
      (value "Insole_electrode_v1")
      (footprint "insole_electrode_v1")
      (libsource (lib "UCL") (part "Insole_electrode_v1"))
    )
    (comp (ref "E239")
      (value "Insole_electrode_v1")
      (footprint "insole_electrode_v1")
      (libsource (lib "UCL") (part "Insole_electrode_v1"))
    )
    (comp (ref "E240")
      (value "Insole_electrode_v1")
      (footprint "insole_electrode_v1")
      (libsource (lib "UCL") (part "Insole_electrode_v1"))
    )
    (comp (ref "E241")
      (value "Insole_electrode_v1")
      (footprint "insole_electrode_v1")
      (libsource (lib "UCL") (part "Insole_electrode_v1"))
    )
    (comp (ref "E242")
      (value "Insole_electrode_v1")
      (footprint "insole_electrode_v1")
      (libsource (lib "UCL") (part "Insole_electrode_v1"))
    )
    (comp (ref "E243")
      (value "Insole_electrode_v1")
      (footprint "insole_electrode_v1")
      (libsource (lib "UCL") (part "Insole_electrode_v1"))
    )
    (comp (ref "E244")
      (value "Insole_electrode_v1")
      (footprint "insole_electrode_v1")
      (libsource (lib "UCL") (part "Insole_electrode_v1"))
    )
    (comp (ref "E245")
      (value "Insole_electrode_v1")
      (footprint "insole_electrode_v1")
      (libsource (lib "UCL") (part "Insole_electrode_v1"))
    )
    (comp (ref "E246")
      (value "Insole_electrode_v1")
      (footprint "insole_electrode_v1")
      (libsource (lib "UCL") (part "Insole_electrode_v1"))
    )
    (comp (ref "E247")
      (value "Insole_electrode_v1")
      (footprint "insole_electrode_v1")
      (libsource (lib "UCL") (part "Insole_electrode_v1"))
    )
    (comp (ref "E248")
      (value "Insole_electrode_v1")
      (footprint "insole_electrode_v1")
      (libsource (lib "UCL") (part "Insole_electrode_v1"))
    )
    (comp (ref "E249")
      (value "Insole_electrode_v1")
      (footprint "insole_electrode_v1")
      (libsource (lib "UCL") (part "Insole_electrode_v1"))
    )
    (comp (ref "E250")
      (value "Insole_electrode_v1")
      (footprint "insole_electrode_v1")
      (libsource (lib "UCL") (part "Insole_electrode_v1"))
    )
    (comp (ref "E251")
      (value "Insole_electrode_v1")
      (footprint "insole_electrode_v1")
      (libsource (lib "UCL") (part "Insole_electrode_v1"))
    )
    (comp (ref "E252")
      (value "Insole_electrode_v1")
      (footprint "insole_electrode_v1")
      (libsource (lib "UCL") (part "Insole_electrode_v1"))
    )
    (comp (ref "E253")
      (value "Insole_electrode_v1")
      (footprint "insole_electrode_v1")
      (libsource (lib "UCL") (part "Insole_electrode_v1"))
    )
    (comp (ref "E254")
      (value "Insole_electrode_v1")
      (footprint "insole_electrode_v1")
      (libsource (lib "UCL") (part "Insole_electrode_v1"))
    )
    (comp (ref "E255")
      (value "Insole_electrode_v1")
      (footprint "insole_electrode_v1")
      (libsource (lib "UCL") (part "Insole_electrode_v1"))
    )
    (comp (ref "E256")
      (value "Insole_electrode_v1")
      (footprint "insole_electrode_v1")
      (libsource (lib "UCL") (part "Insole_electrode_v1"))
    )
    (comp (ref "E257")
      (value "Insole_electrode_v1")
      (footprint "insole_electrode_v1")
      (libsource (lib "UCL") (part "Insole_electrode_v1"))
    )
    (comp (ref "E258")
      (value "Insole_electrode_v1")
      (footprint "insole_electrode_v1")
      (libsource (lib "UCL") (part "Insole_electrode_v1"))
    )
    (comp (ref "E259")
      (value "Insole_electrode_v1")
      (footprint "insole_electrode_v1")
      (libsource (lib "UCL") (part "Insole_electrode_v1"))
    )
    (comp (ref "E260")
      (value "Insole_electrode_v1")
      (footprint "insole_electrode_v1")
      (libsource (lib "UCL") (part "Insole_electrode_v1"))
    )
    (comp (ref "E261")
      (value "Insole_electrode_v1")
      (footprint "insole_electrode_v1")
      (libsource (lib "UCL") (part "Insole_electrode_v1"))
    )
    (comp (ref "E262")
      (value "Insole_electrode_v1")
      (footprint "insole_electrode_v1")
      (libsource (lib "UCL") (part "Insole_electrode_v1"))
    )
    (comp (ref "E263")
      (value "Insole_electrode_v1")
      (footprint "insole_electrode_v1")
      (libsource (lib "UCL") (part "Insole_electrode_v1"))
    )
    (comp (ref "E264")
      (value "Insole_electrode_v1")
      (footprint "insole_electrode_v1")
      (libsource (lib "UCL") (part "Insole_electrode_v1"))
    )
    (comp (ref "E265")
      (value "Insole_electrode_v1")
      (footprint "insole_electrode_v1")
      (libsource (lib "UCL") (part "Insole_electrode_v1"))
    )
    (comp (ref "E266")
      (value "Insole_electrode_v1")
      (footprint "insole_electrode_v1")
      (libsource (lib "UCL") (part "Insole_electrode_v1"))
    )
    (comp (ref "E267")
      (value "Insole_electrode_v1")
      (footprint "insole_electrode_v1")
      (libsource (lib "UCL") (part "Insole_electrode_v1"))
    )
    (comp (ref "E268")
      (value "Insole_electrode_v1")
      (footprint "insole_electrode_v1")
      (libsource (lib "UCL") (part "Insole_electrode_v1"))
    )
    (comp (ref "E269")
      (value "Insole_electrode_v1")
      (footprint "insole_electrode_v1")
      (libsource (lib "UCL") (part "Insole_electrode_v1"))
    )
    (comp (ref "E270")
      (value "Insole_electrode_v1")
      (footprint "insole_electrode_v1")
      (libsource (lib "UCL") (part "Insole_electrode_v1"))
    )
    (comp (ref "E271")
      (value "Insole_electrode_v1")
      (footprint "insole_electrode_v1")
      (libsource (lib "UCL") (part "Insole_electrode_v1"))
    )
    (comp (ref "E272")
      (value "Insole_electrode_v1")
      (footprint "insole_electrode_v1")
      (libsource (lib "UCL") (part "Insole_electrode_v1"))
    )
    (comp (ref "E273")
      (value "Insole_electrode_v1")
      (footprint "insole_electrode_v1")
      (libsource (lib "UCL") (part "Insole_electrode_v1"))
    )
    (comp (ref "E274")
      (value "Insole_electrode_v1")
      (footprint "insole_electrode_v1")
      (libsource (lib "UCL") (part "Insole_electrode_v1"))
    )
    (comp (ref "E275")
      (value "Insole_electrode_v1")
      (footprint "insole_electrode_v1")
      (libsource (lib "UCL") (part "Insole_electrode_v1"))
    )
    (comp (ref "E276")
      (value "Insole_electrode_v1")
      (footprint "insole_electrode_v1")
      (libsource (lib "UCL") (part "Insole_electrode_v1"))
    )
    (comp (ref "E277")
      (value "Insole_electrode_v1")
      (footprint "insole_electrode_v1")
      (libsource (lib "UCL") (part "Insole_electrode_v1"))
    )
    (comp (ref "E278")
      (value "Insole_electrode_v1")
      (footprint "insole_electrode_v1")
      (libsource (lib "UCL") (part "Insole_electrode_v1"))
    )
    (comp (ref "E279")
      (value "Insole_electrode_v1")
      (footprint "insole_electrode_v1")
      (libsource (lib "UCL") (part "Insole_electrode_v1"))
    )
    (comp (ref "E280")
      (value "Insole_electrode_v1")
      (footprint "insole_electrode_v1")
      (libsource (lib "UCL") (part "Insole_electrode_v1"))
    )
    (comp (ref "E281")
      (value "Insole_electrode_v1")
      (footprint "insole_electrode_v1")
      (libsource (lib "UCL") (part "Insole_electrode_v1"))
    )
    (comp (ref "E282")
      (value "Insole_electrode_v1")
      (footprint "insole_electrode_v1")
      (libsource (lib "UCL") (part "Insole_electrode_v1"))
    )
    (comp (ref "E283")
      (value "Insole_electrode_v1")
      (footprint "insole_electrode_v1")
      (libsource (lib "UCL") (part "Insole_electrode_v1"))
    )
    (comp (ref "E284")
      (value "Insole_electrode_v1")
      (footprint "insole_electrode_v1")
      (libsource (lib "UCL") (part "Insole_electrode_v1"))
    )
    (comp (ref "E285")
      (value "Insole_electrode_v1")
      (footprint "insole_electrode_v1")
      (libsource (lib "UCL") (part "Insole_electrode_v1"))
    )
    (comp (ref "E286")
      (value "Insole_electrode_v1")
      (footprint "insole_electrode_v1")
      (libsource (lib "UCL") (part "Insole_electrode_v1"))
    )
    (comp (ref "E287")
      (value "Insole_electrode_v1")
      (footprint "insole_electrode_v1")
      (libsource (lib "UCL") (part "Insole_electrode_v1"))
    )
    (comp (ref "E288")
      (value "Insole_electrode_v1")
      (footprint "insole_electrode_v1")
      (libsource (lib "UCL") (part "Insole_electrode_v1"))
    )
    (comp (ref "E289")
      (value "Insole_electrode_v1")
      (footprint "insole_electrode_v1")
      (libsource (lib "UCL") (part "Insole_electrode_v1"))
    )
    (comp (ref "E290")
      (value "Insole_electrode_v1")
      (footprint "insole_electrode_v1")
      (libsource (lib "UCL") (part "Insole_electrode_v1"))
    )
    (comp (ref "E291")
      (value "Insole_electrode_v1")
      (footprint "insole_electrode_v1")
      (libsource (lib "UCL") (part "Insole_electrode_v1"))
    )
    (comp (ref "E292")
      (value "Insole_electrode_v1")
      (footprint "insole_electrode_v1")
      (libsource (lib "UCL") (part "Insole_electrode_v1"))
    )
    (comp (ref "E293")
      (value "Insole_electrode_v1")
      (footprint "insole_electrode_v1")
      (libsource (lib "UCL") (part "Insole_electrode_v1"))
    )
    (comp (ref "E294")
      (value "Insole_electrode_v1")
      (footprint "insole_electrode_v1")
      (libsource (lib "UCL") (part "Insole_electrode_v1"))
    )
    (comp (ref "E295")
      (value "Insole_electrode_v1")
      (footprint "insole_electrode_v1")
      (libsource (lib "UCL") (part "Insole_electrode_v1"))
    )
    (comp (ref "E296")
      (value "Insole_electrode_v1")
      (footprint "insole_electrode_v1")
      (libsource (lib "UCL") (part "Insole_electrode_v1"))
    )
    (comp (ref "E297")
      (value "Insole_electrode_v1")
      (footprint "insole_electrode_v1")
      (libsource (lib "UCL") (part "Insole_electrode_v1"))
    )
    (comp (ref "E298")
      (value "Insole_electrode_v1")
      (footprint "insole_electrode_v1")
      (libsource (lib "UCL") (part "Insole_electrode_v1"))
    )
    (comp (ref "E299")
      (value "Insole_electrode_v1")
      (footprint "insole_electrode_v1")
      (libsource (lib "UCL") (part "Insole_electrode_v1"))
    )
    (comp (ref "E300")
      (value "Insole_electrode_v1")
      (footprint "insole_electrode_v1")
      (libsource (lib "UCL") (part "Insole_electrode_v1"))
    )
    (comp (ref "E301")
      (value "Insole_electrode_v1")
      (footprint "insole_electrode_v1")
      (libsource (lib "UCL") (part "Insole_electrode_v1"))
    )
    (comp (ref "E302")
      (value "Insole_electrode_v1")
      (footprint "insole_electrode_v1")
      (libsource (lib "UCL") (part "Insole_electrode_v1"))
    )
    (comp (ref "E303")
      (value "Insole_electrode_v1")
      (footprint "insole_electrode_v1")
      (libsource (lib "UCL") (part "Insole_electrode_v1"))
    )
    (comp (ref "E304")
      (value "Insole_electrode_v1")
      (footprint "insole_electrode_v1")
      (libsource (lib "UCL") (part "Insole_electrode_v1"))
    )
    (comp (ref "E305")
      (value "Insole_electrode_v1")
      (footprint "insole_electrode_v1")
      (libsource (lib "UCL") (part "Insole_electrode_v1"))
    )
    (comp (ref "E306")
      (value "Insole_electrode_v1")
      (footprint "insole_electrode_v1")
      (libsource (lib "UCL") (part "Insole_electrode_v1"))
    )
    (comp (ref "E307")
      (value "Insole_electrode_v1")
      (footprint "insole_electrode_v1")
      (libsource (lib "UCL") (part "Insole_electrode_v1"))
    )
    (comp (ref "E308")
      (value "Insole_electrode_v1")
      (footprint "insole_electrode_v1")
      (libsource (lib "UCL") (part "Insole_electrode_v1"))
    )
    (comp (ref "E309")
      (value "Insole_electrode_v1")
      (footprint "insole_electrode_v1")
      (libsource (lib "UCL") (part "Insole_electrode_v1"))
    )
    (comp (ref "E310")
      (value "Insole_electrode_v1")
      (footprint "insole_electrode_v1")
      (libsource (lib "UCL") (part "Insole_electrode_v1"))
    )
    (comp (ref "E311")
      (value "Insole_electrode_v1")
      (footprint "insole_electrode_v1")
      (libsource (lib "UCL") (part "Insole_electrode_v1"))
    )
    (comp (ref "E312")
      (value "Insole_electrode_v1")
      (footprint "insole_electrode_v1")
      (libsource (lib "UCL") (part "Insole_electrode_v1"))
    )
    (comp (ref "E313")
      (value "Insole_electrode_v1")
      (footprint "insole_electrode_v1")
      (libsource (lib "UCL") (part "Insole_electrode_v1"))
    )
    (comp (ref "E314")
      (value "Insole_electrode_v1")
      (footprint "insole_electrode_v1")
      (libsource (lib "UCL") (part "Insole_electrode_v1"))
    )
    (comp (ref "E315")
      (value "Insole_electrode_v1")
      (footprint "insole_electrode_v1")
      (libsource (lib "UCL") (part "Insole_electrode_v1"))
    )
    (comp (ref "E316")
      (value "Insole_electrode_v1")
      (footprint "insole_electrode_v1")
      (libsource (lib "UCL") (part "Insole_electrode_v1"))
    )
    (comp (ref "E317")
      (value "Insole_electrode_v1")
      (footprint "insole_electrode_v1")
      (libsource (lib "UCL") (part "Insole_electrode_v1"))
    )
    (comp (ref "E318")
      (value "Insole_electrode_v1")
      (footprint "insole_electrode_v1")
      (libsource (lib "UCL") (part "Insole_electrode_v1"))
    )
    (comp (ref "E319")
      (value "Insole_electrode_v1")
      (footprint "insole_electrode_v1")
      (libsource (lib "UCL") (part "Insole_electrode_v1"))
    )
    (comp (ref "E320")
      (value "Insole_electrode_v1")
      (footprint "insole_electrode_v1")
      (libsource (lib "UCL") (part "Insole_electrode_v1"))
    )
    (comp (ref "E321")
      (value "Insole_electrode_v1")
      (footprint "insole_electrode_v1")
      (libsource (lib "UCL") (part "Insole_electrode_v1"))
    )
    (comp (ref "E322")
      (value "Insole_electrode_v1")
      (footprint "insole_electrode_v1")
      (libsource (lib "UCL") (part "Insole_electrode_v1"))
    )
    (comp (ref "E323")
      (value "Insole_electrode_v1")
      (footprint "insole_electrode_v1")
      (libsource (lib "UCL") (part "Insole_electrode_v1"))
    )
    (comp (ref "E324")
      (value "Insole_electrode_v1")
      (footprint "insole_electrode_v1")
      (libsource (lib "UCL") (part "Insole_electrode_v1"))
    )
  )
  (nets
    (net (code "1") (name "/Col1") (class "Default")
      (node (ref "E1") (pin "1") (pinfunction "1_1") (pintype "passive"))
      (node (ref "E109") (pin "1") (pinfunction "1_1") (pintype "passive"))
      (node (ref "E127") (pin "1") (pinfunction "1_1") (pintype "passive"))
      (node (ref "E145") (pin "1") (pinfunction "1_1") (pintype "passive"))
      (node (ref "E163") (pin "1") (pinfunction "1_1") (pintype "passive"))
      (node (ref "E181") (pin "1") (pinfunction "1_1") (pintype "passive"))
      (node (ref "E19") (pin "1") (pinfunction "1_1") (pintype "passive"))
      (node (ref "E199") (pin "1") (pinfunction "1_1") (pintype "passive"))
      (node (ref "E217") (pin "1") (pinfunction "1_1") (pintype "passive"))
      (node (ref "E235") (pin "1") (pinfunction "1_1") (pintype "passive"))
      (node (ref "E253") (pin "1") (pinfunction "1_1") (pintype "passive"))
      (node (ref "E271") (pin "1") (pinfunction "1_1") (pintype "passive"))
      (node (ref "E289") (pin "1") (pinfunction "1_1") (pintype "passive"))
      (node (ref "E307") (pin "1") (pinfunction "1_1") (pintype "passive"))
      (node (ref "E37") (pin "1") (pinfunction "1_1") (pintype "passive"))
      (node (ref "E55") (pin "1") (pinfunction "1_1") (pintype "passive"))
      (node (ref "E73") (pin "1") (pinfunction "1_1") (pintype "passive"))
      (node (ref "E91") (pin "1") (pinfunction "1_1") (pintype "passive"))
    )
    (net (code "2") (name "/Col2") (class "Default")
      (node (ref "E110") (pin "1") (pinfunction "1_1") (pintype "passive"))
      (node (ref "E128") (pin "1") (pinfunction "1_1") (pintype "passive"))
      (node (ref "E146") (pin "1") (pinfunction "1_1") (pintype "passive"))
      (node (ref "E164") (pin "1") (pinfunction "1_1") (pintype "passive"))
      (node (ref "E182") (pin "1") (pinfunction "1_1") (pintype "passive"))
      (node (ref "E2") (pin "1") (pinfunction "1_1") (pintype "passive"))
      (node (ref "E20") (pin "1") (pinfunction "1_1") (pintype "passive"))
      (node (ref "E200") (pin "1") (pinfunction "1_1") (pintype "passive"))
      (node (ref "E218") (pin "1") (pinfunction "1_1") (pintype "passive"))
      (node (ref "E236") (pin "1") (pinfunction "1_1") (pintype "passive"))
      (node (ref "E254") (pin "1") (pinfunction "1_1") (pintype "passive"))
      (node (ref "E272") (pin "1") (pinfunction "1_1") (pintype "passive"))
      (node (ref "E290") (pin "1") (pinfunction "1_1") (pintype "passive"))
      (node (ref "E308") (pin "1") (pinfunction "1_1") (pintype "passive"))
      (node (ref "E38") (pin "1") (pinfunction "1_1") (pintype "passive"))
      (node (ref "E56") (pin "1") (pinfunction "1_1") (pintype "passive"))
      (node (ref "E74") (pin "1") (pinfunction "1_1") (pintype "passive"))
      (node (ref "E92") (pin "1") (pinfunction "1_1") (pintype "passive"))
    )
    (net (code "3") (name "/Col3") (class "Default")
      (node (ref "E111") (pin "1") (pinfunction "1_1") (pintype "passive"))
      (node (ref "E129") (pin "1") (pinfunction "1_1") (pintype "passive"))
      (node (ref "E147") (pin "1") (pinfunction "1_1") (pintype "passive"))
      (node (ref "E165") (pin "1") (pinfunction "1_1") (pintype "passive"))
      (node (ref "E183") (pin "1") (pinfunction "1_1") (pintype "passive"))
      (node (ref "E201") (pin "1") (pinfunction "1_1") (pintype "passive"))
      (node (ref "E21") (pin "1") (pinfunction "1_1") (pintype "passive"))
      (node (ref "E219") (pin "1") (pinfunction "1_1") (pintype "passive"))
      (node (ref "E237") (pin "1") (pinfunction "1_1") (pintype "passive"))
      (node (ref "E255") (pin "1") (pinfunction "1_1") (pintype "passive"))
      (node (ref "E273") (pin "1") (pinfunction "1_1") (pintype "passive"))
      (node (ref "E291") (pin "1") (pinfunction "1_1") (pintype "passive"))
      (node (ref "E3") (pin "1") (pinfunction "1_1") (pintype "passive"))
      (node (ref "E309") (pin "1") (pinfunction "1_1") (pintype "passive"))
      (node (ref "E39") (pin "1") (pinfunction "1_1") (pintype "passive"))
      (node (ref "E57") (pin "1") (pinfunction "1_1") (pintype "passive"))
      (node (ref "E75") (pin "1") (pinfunction "1_1") (pintype "passive"))
      (node (ref "E93") (pin "1") (pinfunction "1_1") (pintype "passive"))
    )
    (net (code "4") (name "/Col4") (class "Default")
      (node (ref "E112") (pin "1") (pinfunction "1_1") (pintype "passive"))
      (node (ref "E130") (pin "1") (pinfunction "1_1") (pintype "passive"))
      (node (ref "E148") (pin "1") (pinfunction "1_1") (pintype "passive"))
      (node (ref "E166") (pin "1") (pinfunction "1_1") (pintype "passive"))
      (node (ref "E184") (pin "1") (pinfunction "1_1") (pintype "passive"))
      (node (ref "E202") (pin "1") (pinfunction "1_1") (pintype "passive"))
      (node (ref "E22") (pin "1") (pinfunction "1_1") (pintype "passive"))
      (node (ref "E220") (pin "1") (pinfunction "1_1") (pintype "passive"))
      (node (ref "E238") (pin "1") (pinfunction "1_1") (pintype "passive"))
      (node (ref "E256") (pin "1") (pinfunction "1_1") (pintype "passive"))
      (node (ref "E274") (pin "1") (pinfunction "1_1") (pintype "passive"))
      (node (ref "E292") (pin "1") (pinfunction "1_1") (pintype "passive"))
      (node (ref "E310") (pin "1") (pinfunction "1_1") (pintype "passive"))
      (node (ref "E4") (pin "1") (pinfunction "1_1") (pintype "passive"))
      (node (ref "E40") (pin "1") (pinfunction "1_1") (pintype "passive"))
      (node (ref "E58") (pin "1") (pinfunction "1_1") (pintype "passive"))
      (node (ref "E76") (pin "1") (pinfunction "1_1") (pintype "passive"))
      (node (ref "E94") (pin "1") (pinfunction "1_1") (pintype "passive"))
    )
    (net (code "5") (name "/Col5") (class "Default")
      (node (ref "E113") (pin "1") (pinfunction "1_1") (pintype "passive"))
      (node (ref "E131") (pin "1") (pinfunction "1_1") (pintype "passive"))
      (node (ref "E149") (pin "1") (pinfunction "1_1") (pintype "passive"))
      (node (ref "E167") (pin "1") (pinfunction "1_1") (pintype "passive"))
      (node (ref "E185") (pin "1") (pinfunction "1_1") (pintype "passive"))
      (node (ref "E203") (pin "1") (pinfunction "1_1") (pintype "passive"))
      (node (ref "E221") (pin "1") (pinfunction "1_1") (pintype "passive"))
      (node (ref "E23") (pin "1") (pinfunction "1_1") (pintype "passive"))
      (node (ref "E239") (pin "1") (pinfunction "1_1") (pintype "passive"))
      (node (ref "E257") (pin "1") (pinfunction "1_1") (pintype "passive"))
      (node (ref "E275") (pin "1") (pinfunction "1_1") (pintype "passive"))
      (node (ref "E293") (pin "1") (pinfunction "1_1") (pintype "passive"))
      (node (ref "E311") (pin "1") (pinfunction "1_1") (pintype "passive"))
      (node (ref "E41") (pin "1") (pinfunction "1_1") (pintype "passive"))
      (node (ref "E5") (pin "1") (pinfunction "1_1") (pintype "passive"))
      (node (ref "E59") (pin "1") (pinfunction "1_1") (pintype "passive"))
      (node (ref "E77") (pin "1") (pinfunction "1_1") (pintype "passive"))
      (node (ref "E95") (pin "1") (pinfunction "1_1") (pintype "passive"))
    )
    (net (code "6") (name "/Col6") (class "Default")
      (node (ref "E114") (pin "1") (pinfunction "1_1") (pintype "passive"))
      (node (ref "E132") (pin "1") (pinfunction "1_1") (pintype "passive"))
      (node (ref "E150") (pin "1") (pinfunction "1_1") (pintype "passive"))
      (node (ref "E168") (pin "1") (pinfunction "1_1") (pintype "passive"))
      (node (ref "E186") (pin "1") (pinfunction "1_1") (pintype "passive"))
      (node (ref "E204") (pin "1") (pinfunction "1_1") (pintype "passive"))
      (node (ref "E222") (pin "1") (pinfunction "1_1") (pintype "passive"))
      (node (ref "E24") (pin "1") (pinfunction "1_1") (pintype "passive"))
      (node (ref "E240") (pin "1") (pinfunction "1_1") (pintype "passive"))
      (node (ref "E258") (pin "1") (pinfunction "1_1") (pintype "passive"))
      (node (ref "E276") (pin "1") (pinfunction "1_1") (pintype "passive"))
      (node (ref "E294") (pin "1") (pinfunction "1_1") (pintype "passive"))
      (node (ref "E312") (pin "1") (pinfunction "1_1") (pintype "passive"))
      (node (ref "E42") (pin "1") (pinfunction "1_1") (pintype "passive"))
      (node (ref "E6") (pin "1") (pinfunction "1_1") (pintype "passive"))
      (node (ref "E60") (pin "1") (pinfunction "1_1") (pintype "passive"))
      (node (ref "E78") (pin "1") (pinfunction "1_1") (pintype "passive"))
      (node (ref "E96") (pin "1") (pinfunction "1_1") (pintype "passive"))
    )
    (net (code "7") (name "/Col7") (class "Default")
      (node (ref "E115") (pin "1") (pinfunction "1_1") (pintype "passive"))
      (node (ref "E133") (pin "1") (pinfunction "1_1") (pintype "passive"))
      (node (ref "E151") (pin "1") (pinfunction "1_1") (pintype "passive"))
      (node (ref "E169") (pin "1") (pinfunction "1_1") (pintype "passive"))
      (node (ref "E187") (pin "1") (pinfunction "1_1") (pintype "passive"))
      (node (ref "E205") (pin "1") (pinfunction "1_1") (pintype "passive"))
      (node (ref "E223") (pin "1") (pinfunction "1_1") (pintype "passive"))
      (node (ref "E241") (pin "1") (pinfunction "1_1") (pintype "passive"))
      (node (ref "E25") (pin "1") (pinfunction "1_1") (pintype "passive"))
      (node (ref "E259") (pin "1") (pinfunction "1_1") (pintype "passive"))
      (node (ref "E277") (pin "1") (pinfunction "1_1") (pintype "passive"))
      (node (ref "E295") (pin "1") (pinfunction "1_1") (pintype "passive"))
      (node (ref "E313") (pin "1") (pinfunction "1_1") (pintype "passive"))
      (node (ref "E43") (pin "1") (pinfunction "1_1") (pintype "passive"))
      (node (ref "E61") (pin "1") (pinfunction "1_1") (pintype "passive"))
      (node (ref "E7") (pin "1") (pinfunction "1_1") (pintype "passive"))
      (node (ref "E79") (pin "1") (pinfunction "1_1") (pintype "passive"))
      (node (ref "E97") (pin "1") (pinfunction "1_1") (pintype "passive"))
    )
    (net (code "8") (name "/Col8") (class "Default")
      (node (ref "E116") (pin "1") (pinfunction "1_1") (pintype "passive"))
      (node (ref "E134") (pin "1") (pinfunction "1_1") (pintype "passive"))
      (node (ref "E152") (pin "1") (pinfunction "1_1") (pintype "passive"))
      (node (ref "E170") (pin "1") (pinfunction "1_1") (pintype "passive"))
      (node (ref "E188") (pin "1") (pinfunction "1_1") (pintype "passive"))
      (node (ref "E206") (pin "1") (pinfunction "1_1") (pintype "passive"))
      (node (ref "E224") (pin "1") (pinfunction "1_1") (pintype "passive"))
      (node (ref "E242") (pin "1") (pinfunction "1_1") (pintype "passive"))
      (node (ref "E26") (pin "1") (pinfunction "1_1") (pintype "passive"))
      (node (ref "E260") (pin "1") (pinfunction "1_1") (pintype "passive"))
      (node (ref "E278") (pin "1") (pinfunction "1_1") (pintype "passive"))
      (node (ref "E296") (pin "1") (pinfunction "1_1") (pintype "passive"))
      (node (ref "E314") (pin "1") (pinfunction "1_1") (pintype "passive"))
      (node (ref "E44") (pin "1") (pinfunction "1_1") (pintype "passive"))
      (node (ref "E62") (pin "1") (pinfunction "1_1") (pintype "passive"))
      (node (ref "E8") (pin "1") (pinfunction "1_1") (pintype "passive"))
      (node (ref "E80") (pin "1") (pinfunction "1_1") (pintype "passive"))
      (node (ref "E98") (pin "1") (pinfunction "1_1") (pintype "passive"))
    )
    (net (code "9") (name "/Col9") (class "Default")
      (node (ref "E117") (pin "1") (pinfunction "1_1") (pintype "passive"))
      (node (ref "E135") (pin "1") (pinfunction "1_1") (pintype "passive"))
      (node (ref "E153") (pin "1") (pinfunction "1_1") (pintype "passive"))
      (node (ref "E171") (pin "1") (pinfunction "1_1") (pintype "passive"))
      (node (ref "E189") (pin "1") (pinfunction "1_1") (pintype "passive"))
      (node (ref "E207") (pin "1") (pinfunction "1_1") (pintype "passive"))
      (node (ref "E225") (pin "1") (pinfunction "1_1") (pintype "passive"))
      (node (ref "E243") (pin "1") (pinfunction "1_1") (pintype "passive"))
      (node (ref "E261") (pin "1") (pinfunction "1_1") (pintype "passive"))
      (node (ref "E27") (pin "1") (pinfunction "1_1") (pintype "passive"))
      (node (ref "E279") (pin "1") (pinfunction "1_1") (pintype "passive"))
      (node (ref "E297") (pin "1") (pinfunction "1_1") (pintype "passive"))
      (node (ref "E315") (pin "1") (pinfunction "1_1") (pintype "passive"))
      (node (ref "E45") (pin "1") (pinfunction "1_1") (pintype "passive"))
      (node (ref "E63") (pin "1") (pinfunction "1_1") (pintype "passive"))
      (node (ref "E81") (pin "1") (pinfunction "1_1") (pintype "passive"))
      (node (ref "E9") (pin "1") (pinfunction "1_1") (pintype "passive"))
      (node (ref "E99") (pin "1") (pinfunction "1_1") (pintype "passive"))
    )
    (net (code "10") (name "/Col10") (class "Default")
      (node (ref "E10") (pin "1") (pinfunction "1_1") (pintype "passive"))
      (node (ref "E100") (pin "1") (pinfunction "1_1") (pintype "passive"))
      (node (ref "E118") (pin "1") (pinfunction "1_1") (pintype "passive"))
      (node (ref "E136") (pin "1") (pinfunction "1_1") (pintype "passive"))
      (node (ref "E154") (pin "1") (pinfunction "1_1") (pintype "passive"))
      (node (ref "E172") (pin "1") (pinfunction "1_1") (pintype "passive"))
      (node (ref "E190") (pin "1") (pinfunction "1_1") (pintype "passive"))
      (node (ref "E208") (pin "1") (pinfunction "1_1") (pintype "passive"))
      (node (ref "E226") (pin "1") (pinfunction "1_1") (pintype "passive"))
      (node (ref "E244") (pin "1") (pinfunction "1_1") (pintype "passive"))
      (node (ref "E262") (pin "1") (pinfunction "1_1") (pintype "passive"))
      (node (ref "E28") (pin "1") (pinfunction "1_1") (pintype "passive"))
      (node (ref "E280") (pin "1") (pinfunction "1_1") (pintype "passive"))
      (node (ref "E298") (pin "1") (pinfunction "1_1") (pintype "passive"))
      (node (ref "E316") (pin "1") (pinfunction "1_1") (pintype "passive"))
      (node (ref "E46") (pin "1") (pinfunction "1_1") (pintype "passive"))
      (node (ref "E64") (pin "1") (pinfunction "1_1") (pintype "passive"))
      (node (ref "E82") (pin "1") (pinfunction "1_1") (pintype "passive"))
    )
    (net (code "11") (name "/Col11") (class "Default")
      (node (ref "E101") (pin "1") (pinfunction "1_1") (pintype "passive"))
      (node (ref "E11") (pin "1") (pinfunction "1_1") (pintype "passive"))
      (node (ref "E119") (pin "1") (pinfunction "1_1") (pintype "passive"))
      (node (ref "E137") (pin "1") (pinfunction "1_1") (pintype "passive"))
      (node (ref "E155") (pin "1") (pinfunction "1_1") (pintype "passive"))
      (node (ref "E173") (pin "1") (pinfunction "1_1") (pintype "passive"))
      (node (ref "E191") (pin "1") (pinfunction "1_1") (pintype "passive"))
      (node (ref "E209") (pin "1") (pinfunction "1_1") (pintype "passive"))
      (node (ref "E227") (pin "1") (pinfunction "1_1") (pintype "passive"))
      (node (ref "E245") (pin "1") (pinfunction "1_1") (pintype "passive"))
      (node (ref "E263") (pin "1") (pinfunction "1_1") (pintype "passive"))
      (node (ref "E281") (pin "1") (pinfunction "1_1") (pintype "passive"))
      (node (ref "E29") (pin "1") (pinfunction "1_1") (pintype "passive"))
      (node (ref "E299") (pin "1") (pinfunction "1_1") (pintype "passive"))
      (node (ref "E317") (pin "1") (pinfunction "1_1") (pintype "passive"))
      (node (ref "E47") (pin "1") (pinfunction "1_1") (pintype "passive"))
      (node (ref "E65") (pin "1") (pinfunction "1_1") (pintype "passive"))
      (node (ref "E83") (pin "1") (pinfunction "1_1") (pintype "passive"))
    )
    (net (code "12") (name "/Col12") (class "Default")
      (node (ref "E102") (pin "1") (pinfunction "1_1") (pintype "passive"))
      (node (ref "E12") (pin "1") (pinfunction "1_1") (pintype "passive"))
      (node (ref "E120") (pin "1") (pinfunction "1_1") (pintype "passive"))
      (node (ref "E138") (pin "1") (pinfunction "1_1") (pintype "passive"))
      (node (ref "E156") (pin "1") (pinfunction "1_1") (pintype "passive"))
      (node (ref "E174") (pin "1") (pinfunction "1_1") (pintype "passive"))
      (node (ref "E192") (pin "1") (pinfunction "1_1") (pintype "passive"))
      (node (ref "E210") (pin "1") (pinfunction "1_1") (pintype "passive"))
      (node (ref "E228") (pin "1") (pinfunction "1_1") (pintype "passive"))
      (node (ref "E246") (pin "1") (pinfunction "1_1") (pintype "passive"))
      (node (ref "E264") (pin "1") (pinfunction "1_1") (pintype "passive"))
      (node (ref "E282") (pin "1") (pinfunction "1_1") (pintype "passive"))
      (node (ref "E30") (pin "1") (pinfunction "1_1") (pintype "passive"))
      (node (ref "E300") (pin "1") (pinfunction "1_1") (pintype "passive"))
      (node (ref "E318") (pin "1") (pinfunction "1_1") (pintype "passive"))
      (node (ref "E48") (pin "1") (pinfunction "1_1") (pintype "passive"))
      (node (ref "E66") (pin "1") (pinfunction "1_1") (pintype "passive"))
      (node (ref "E84") (pin "1") (pinfunction "1_1") (pintype "passive"))
    )
    (net (code "13") (name "/Col13") (class "Default")
      (node (ref "E103") (pin "1") (pinfunction "1_1") (pintype "passive"))
      (node (ref "E121") (pin "1") (pinfunction "1_1") (pintype "passive"))
      (node (ref "E13") (pin "1") (pinfunction "1_1") (pintype "passive"))
      (node (ref "E139") (pin "1") (pinfunction "1_1") (pintype "passive"))
      (node (ref "E157") (pin "1") (pinfunction "1_1") (pintype "passive"))
      (node (ref "E175") (pin "1") (pinfunction "1_1") (pintype "passive"))
      (node (ref "E193") (pin "1") (pinfunction "1_1") (pintype "passive"))
      (node (ref "E211") (pin "1") (pinfunction "1_1") (pintype "passive"))
      (node (ref "E229") (pin "1") (pinfunction "1_1") (pintype "passive"))
      (node (ref "E247") (pin "1") (pinfunction "1_1") (pintype "passive"))
      (node (ref "E265") (pin "1") (pinfunction "1_1") (pintype "passive"))
      (node (ref "E283") (pin "1") (pinfunction "1_1") (pintype "passive"))
      (node (ref "E301") (pin "1") (pinfunction "1_1") (pintype "passive"))
      (node (ref "E31") (pin "1") (pinfunction "1_1") (pintype "passive"))
      (node (ref "E319") (pin "1") (pinfunction "1_1") (pintype "passive"))
      (node (ref "E49") (pin "1") (pinfunction "1_1") (pintype "passive"))
      (node (ref "E67") (pin "1") (pinfunction "1_1") (pintype "passive"))
      (node (ref "E85") (pin "1") (pinfunction "1_1") (pintype "passive"))
    )
    (net (code "14") (name "/Col14") (class "Default")
      (node (ref "E104") (pin "1") (pinfunction "1_1") (pintype "passive"))
      (node (ref "E122") (pin "1") (pinfunction "1_1") (pintype "passive"))
      (node (ref "E14") (pin "1") (pinfunction "1_1") (pintype "passive"))
      (node (ref "E140") (pin "1") (pinfunction "1_1") (pintype "passive"))
      (node (ref "E158") (pin "1") (pinfunction "1_1") (pintype "passive"))
      (node (ref "E176") (pin "1") (pinfunction "1_1") (pintype "passive"))
      (node (ref "E194") (pin "1") (pinfunction "1_1") (pintype "passive"))
      (node (ref "E212") (pin "1") (pinfunction "1_1") (pintype "passive"))
      (node (ref "E230") (pin "1") (pinfunction "1_1") (pintype "passive"))
      (node (ref "E248") (pin "1") (pinfunction "1_1") (pintype "passive"))
      (node (ref "E266") (pin "1") (pinfunction "1_1") (pintype "passive"))
      (node (ref "E284") (pin "1") (pinfunction "1_1") (pintype "passive"))
      (node (ref "E302") (pin "1") (pinfunction "1_1") (pintype "passive"))
      (node (ref "E32") (pin "1") (pinfunction "1_1") (pintype "passive"))
      (node (ref "E320") (pin "1") (pinfunction "1_1") (pintype "passive"))
      (node (ref "E50") (pin "1") (pinfunction "1_1") (pintype "passive"))
      (node (ref "E68") (pin "1") (pinfunction "1_1") (pintype "passive"))
      (node (ref "E86") (pin "1") (pinfunction "1_1") (pintype "passive"))
    )
    (net (code "15") (name "/Col15") (class "Default")
      (node (ref "E105") (pin "1") (pinfunction "1_1") (pintype "passive"))
      (node (ref "E123") (pin "1") (pinfunction "1_1") (pintype "passive"))
      (node (ref "E141") (pin "1") (pinfunction "1_1") (pintype "passive"))
      (node (ref "E15") (pin "1") (pinfunction "1_1") (pintype "passive"))
      (node (ref "E159") (pin "1") (pinfunction "1_1") (pintype "passive"))
      (node (ref "E177") (pin "1") (pinfunction "1_1") (pintype "passive"))
      (node (ref "E195") (pin "1") (pinfunction "1_1") (pintype "passive"))
      (node (ref "E213") (pin "1") (pinfunction "1_1") (pintype "passive"))
      (node (ref "E231") (pin "1") (pinfunction "1_1") (pintype "passive"))
      (node (ref "E249") (pin "1") (pinfunction "1_1") (pintype "passive"))
      (node (ref "E267") (pin "1") (pinfunction "1_1") (pintype "passive"))
      (node (ref "E285") (pin "1") (pinfunction "1_1") (pintype "passive"))
      (node (ref "E303") (pin "1") (pinfunction "1_1") (pintype "passive"))
      (node (ref "E321") (pin "1") (pinfunction "1_1") (pintype "passive"))
      (node (ref "E33") (pin "1") (pinfunction "1_1") (pintype "passive"))
      (node (ref "E51") (pin "1") (pinfunction "1_1") (pintype "passive"))
      (node (ref "E69") (pin "1") (pinfunction "1_1") (pintype "passive"))
      (node (ref "E87") (pin "1") (pinfunction "1_1") (pintype "passive"))
    )
    (net (code "16") (name "/Col16") (class "Default")
      (node (ref "E106") (pin "1") (pinfunction "1_1") (pintype "passive"))
      (node (ref "E124") (pin "1") (pinfunction "1_1") (pintype "passive"))
      (node (ref "E142") (pin "1") (pinfunction "1_1") (pintype "passive"))
      (node (ref "E16") (pin "1") (pinfunction "1_1") (pintype "passive"))
      (node (ref "E160") (pin "1") (pinfunction "1_1") (pintype "passive"))
      (node (ref "E178") (pin "1") (pinfunction "1_1") (pintype "passive"))
      (node (ref "E196") (pin "1") (pinfunction "1_1") (pintype "passive"))
      (node (ref "E214") (pin "1") (pinfunction "1_1") (pintype "passive"))
      (node (ref "E232") (pin "1") (pinfunction "1_1") (pintype "passive"))
      (node (ref "E250") (pin "1") (pinfunction "1_1") (pintype "passive"))
      (node (ref "E268") (pin "1") (pinfunction "1_1") (pintype "passive"))
      (node (ref "E286") (pin "1") (pinfunction "1_1") (pintype "passive"))
      (node (ref "E304") (pin "1") (pinfunction "1_1") (pintype "passive"))
      (node (ref "E322") (pin "1") (pinfunction "1_1") (pintype "passive"))
      (node (ref "E34") (pin "1") (pinfunction "1_1") (pintype "passive"))
      (node (ref "E52") (pin "1") (pinfunction "1_1") (pintype "passive"))
      (node (ref "E70") (pin "1") (pinfunction "1_1") (pintype "passive"))
      (node (ref "E88") (pin "1") (pinfunction "1_1") (pintype "passive"))
    )
    (net (code "17") (name "/Col17") (class "Default")
      (node (ref "E107") (pin "1") (pinfunction "1_1") (pintype "passive"))
      (node (ref "E125") (pin "1") (pinfunction "1_1") (pintype "passive"))
      (node (ref "E143") (pin "1") (pinfunction "1_1") (pintype "passive"))
      (node (ref "E161") (pin "1") (pinfunction "1_1") (pintype "passive"))
      (node (ref "E17") (pin "1") (pinfunction "1_1") (pintype "passive"))
      (node (ref "E179") (pin "1") (pinfunction "1_1") (pintype "passive"))
      (node (ref "E197") (pin "1") (pinfunction "1_1") (pintype "passive"))
      (node (ref "E215") (pin "1") (pinfunction "1_1") (pintype "passive"))
      (node (ref "E233") (pin "1") (pinfunction "1_1") (pintype "passive"))
      (node (ref "E251") (pin "1") (pinfunction "1_1") (pintype "passive"))
      (node (ref "E269") (pin "1") (pinfunction "1_1") (pintype "passive"))
      (node (ref "E287") (pin "1") (pinfunction "1_1") (pintype "passive"))
      (node (ref "E305") (pin "1") (pinfunction "1_1") (pintype "passive"))
      (node (ref "E323") (pin "1") (pinfunction "1_1") (pintype "passive"))
      (node (ref "E35") (pin "1") (pinfunction "1_1") (pintype "passive"))
      (node (ref "E53") (pin "1") (pinfunction "1_1") (pintype "passive"))
      (node (ref "E71") (pin "1") (pinfunction "1_1") (pintype "passive"))
      (node (ref "E89") (pin "1") (pinfunction "1_1") (pintype "passive"))
    )
    (net (code "18") (name "/Col18") (class "Default")
      (node (ref "E108") (pin "1") (pinfunction "1_1") (pintype "passive"))
      (node (ref "E126") (pin "1") (pinfunction "1_1") (pintype "passive"))
      (node (ref "E144") (pin "1") (pinfunction "1_1") (pintype "passive"))
      (node (ref "E162") (pin "1") (pinfunction "1_1") (pintype "passive"))
      (node (ref "E18") (pin "1") (pinfunction "1_1") (pintype "passive"))
      (node (ref "E180") (pin "1") (pinfunction "1_1") (pintype "passive"))
      (node (ref "E198") (pin "1") (pinfunction "1_1") (pintype "passive"))
      (node (ref "E216") (pin "1") (pinfunction "1_1") (pintype "passive"))
      (node (ref "E234") (pin "1") (pinfunction "1_1") (pintype "passive"))
      (node (ref "E252") (pin "1") (pinfunction "1_1") (pintype "passive"))
      (node (ref "E270") (pin "1") (pinfunction "1_1") (pintype "passive"))
      (node (ref "E288") (pin "1") (pinfunction "1_1") (pintype "passive"))
      (node (ref "E306") (pin "1") (pinfunction "1_1") (pintype "passive"))
      (node (ref "E324") (pin "1") (pinfunction "1_1") (pintype "passive"))
      (node (ref "E36") (pin "1") (pinfunction "1_1") (pintype "passive"))
      (node (ref "E54") (pin "1") (pinfunction "1_1") (pintype "passive"))
      (node (ref "E72") (pin "1") (pinfunction "1_1") (pintype "passive"))
      (node (ref "E90") (pin "1") (pinfunction "1_1") (pintype "passive"))
    )
    (net (code "19") (name "/Row1") (class "Default")
      (node (ref "E1") (pin "0") (pinfunction "0_0") (pintype "passive"))
      (node (ref "E10") (pin "0") (pinfunction "0_0") (pintype "passive"))
      (node (ref "E11") (pin "0") (pinfunction "0_0") (pintype "passive"))
      (node (ref "E12") (pin "0") (pinfunction "0_0") (pintype "passive"))
      (node (ref "E13") (pin "0") (pinfunction "0_0") (pintype "passive"))
      (node (ref "E14") (pin "0") (pinfunction "0_0") (pintype "passive"))
      (node (ref "E15") (pin "0") (pinfunction "0_0") (pintype "passive"))
      (node (ref "E16") (pin "0") (pinfunction "0_0") (pintype "passive"))
      (node (ref "E17") (pin "0") (pinfunction "0_0") (pintype "passive"))
      (node (ref "E18") (pin "0") (pinfunction "0_0") (pintype "passive"))
      (node (ref "E2") (pin "0") (pinfunction "0_0") (pintype "passive"))
      (node (ref "E3") (pin "0") (pinfunction "0_0") (pintype "passive"))
      (node (ref "E4") (pin "0") (pinfunction "0_0") (pintype "passive"))
      (node (ref "E5") (pin "0") (pinfunction "0_0") (pintype "passive"))
      (node (ref "E6") (pin "0") (pinfunction "0_0") (pintype "passive"))
      (node (ref "E7") (pin "0") (pinfunction "0_0") (pintype "passive"))
      (node (ref "E8") (pin "0") (pinfunction "0_0") (pintype "passive"))
      (node (ref "E9") (pin "0") (pinfunction "0_0") (pintype "passive"))
    )
    (net (code "20") (name "/Row2") (class "Default")
      (node (ref "E19") (pin "0") (pinfunction "0_0") (pintype "passive"))
      (node (ref "E20") (pin "0") (pinfunction "0_0") (pintype "passive"))
      (node (ref "E21") (pin "0") (pinfunction "0_0") (pintype "passive"))
      (node (ref "E22") (pin "0") (pinfunction "0_0") (pintype "passive"))
      (node (ref "E23") (pin "0") (pinfunction "0_0") (pintype "passive"))
      (node (ref "E24") (pin "0") (pinfunction "0_0") (pintype "passive"))
      (node (ref "E25") (pin "0") (pinfunction "0_0") (pintype "passive"))
      (node (ref "E26") (pin "0") (pinfunction "0_0") (pintype "passive"))
      (node (ref "E27") (pin "0") (pinfunction "0_0") (pintype "passive"))
      (node (ref "E28") (pin "0") (pinfunction "0_0") (pintype "passive"))
      (node (ref "E29") (pin "0") (pinfunction "0_0") (pintype "passive"))
      (node (ref "E30") (pin "0") (pinfunction "0_0") (pintype "passive"))
      (node (ref "E31") (pin "0") (pinfunction "0_0") (pintype "passive"))
      (node (ref "E32") (pin "0") (pinfunction "0_0") (pintype "passive"))
      (node (ref "E33") (pin "0") (pinfunction "0_0") (pintype "passive"))
      (node (ref "E34") (pin "0") (pinfunction "0_0") (pintype "passive"))
      (node (ref "E35") (pin "0") (pinfunction "0_0") (pintype "passive"))
      (node (ref "E36") (pin "0") (pinfunction "0_0") (pintype "passive"))
    )
    (net (code "21") (name "/Row3") (class "Default")
      (node (ref "E37") (pin "0") (pinfunction "0_0") (pintype "passive"))
      (node (ref "E38") (pin "0") (pinfunction "0_0") (pintype "passive"))
      (node (ref "E39") (pin "0") (pinfunction "0_0") (pintype "passive"))
      (node (ref "E40") (pin "0") (pinfunction "0_0") (pintype "passive"))
      (node (ref "E41") (pin "0") (pinfunction "0_0") (pintype "passive"))
      (node (ref "E42") (pin "0") (pinfunction "0_0") (pintype "passive"))
      (node (ref "E43") (pin "0") (pinfunction "0_0") (pintype "passive"))
      (node (ref "E44") (pin "0") (pinfunction "0_0") (pintype "passive"))
      (node (ref "E45") (pin "0") (pinfunction "0_0") (pintype "passive"))
      (node (ref "E46") (pin "0") (pinfunction "0_0") (pintype "passive"))
      (node (ref "E47") (pin "0") (pinfunction "0_0") (pintype "passive"))
      (node (ref "E48") (pin "0") (pinfunction "0_0") (pintype "passive"))
      (node (ref "E49") (pin "0") (pinfunction "0_0") (pintype "passive"))
      (node (ref "E50") (pin "0") (pinfunction "0_0") (pintype "passive"))
      (node (ref "E51") (pin "0") (pinfunction "0_0") (pintype "passive"))
      (node (ref "E52") (pin "0") (pinfunction "0_0") (pintype "passive"))
      (node (ref "E53") (pin "0") (pinfunction "0_0") (pintype "passive"))
      (node (ref "E54") (pin "0") (pinfunction "0_0") (pintype "passive"))
    )
    (net (code "22") (name "/Row4") (class "Default")
      (node (ref "E55") (pin "0") (pinfunction "0_0") (pintype "passive"))
      (node (ref "E56") (pin "0") (pinfunction "0_0") (pintype "passive"))
      (node (ref "E57") (pin "0") (pinfunction "0_0") (pintype "passive"))
      (node (ref "E58") (pin "0") (pinfunction "0_0") (pintype "passive"))
      (node (ref "E59") (pin "0") (pinfunction "0_0") (pintype "passive"))
      (node (ref "E60") (pin "0") (pinfunction "0_0") (pintype "passive"))
      (node (ref "E61") (pin "0") (pinfunction "0_0") (pintype "passive"))
      (node (ref "E62") (pin "0") (pinfunction "0_0") (pintype "passive"))
      (node (ref "E63") (pin "0") (pinfunction "0_0") (pintype "passive"))
      (node (ref "E64") (pin "0") (pinfunction "0_0") (pintype "passive"))
      (node (ref "E65") (pin "0") (pinfunction "0_0") (pintype "passive"))
      (node (ref "E66") (pin "0") (pinfunction "0_0") (pintype "passive"))
      (node (ref "E67") (pin "0") (pinfunction "0_0") (pintype "passive"))
      (node (ref "E68") (pin "0") (pinfunction "0_0") (pintype "passive"))
      (node (ref "E69") (pin "0") (pinfunction "0_0") (pintype "passive"))
      (node (ref "E70") (pin "0") (pinfunction "0_0") (pintype "passive"))
      (node (ref "E71") (pin "0") (pinfunction "0_0") (pintype "passive"))
      (node (ref "E72") (pin "0") (pinfunction "0_0") (pintype "passive"))
    )
    (net (code "23") (name "/Row5") (class "Default")
      (node (ref "E73") (pin "0") (pinfunction "0_0") (pintype "passive"))
      (node (ref "E74") (pin "0") (pinfunction "0_0") (pintype "passive"))
      (node (ref "E75") (pin "0") (pinfunction "0_0") (pintype "passive"))
      (node (ref "E76") (pin "0") (pinfunction "0_0") (pintype "passive"))
      (node (ref "E77") (pin "0") (pinfunction "0_0") (pintype "passive"))
      (node (ref "E78") (pin "0") (pinfunction "0_0") (pintype "passive"))
      (node (ref "E79") (pin "0") (pinfunction "0_0") (pintype "passive"))
      (node (ref "E80") (pin "0") (pinfunction "0_0") (pintype "passive"))
      (node (ref "E81") (pin "0") (pinfunction "0_0") (pintype "passive"))
      (node (ref "E82") (pin "0") (pinfunction "0_0") (pintype "passive"))
      (node (ref "E83") (pin "0") (pinfunction "0_0") (pintype "passive"))
      (node (ref "E84") (pin "0") (pinfunction "0_0") (pintype "passive"))
      (node (ref "E85") (pin "0") (pinfunction "0_0") (pintype "passive"))
      (node (ref "E86") (pin "0") (pinfunction "0_0") (pintype "passive"))
      (node (ref "E87") (pin "0") (pinfunction "0_0") (pintype "passive"))
      (node (ref "E88") (pin "0") (pinfunction "0_0") (pintype "passive"))
      (node (ref "E89") (pin "0") (pinfunction "0_0") (pintype "passive"))
      (node (ref "E90") (pin "0") (pinfunction "0_0") (pintype "passive"))
    )
    (net (code "24") (name "/Row6") (class "Default")
      (node (ref "E100") (pin "0") (pinfunction "0_0") (pintype "passive"))
      (node (ref "E101") (pin "0") (pinfunction "0_0") (pintype "passive"))
      (node (ref "E102") (pin "0") (pinfunction "0_0") (pintype "passive"))
      (node (ref "E103") (pin "0") (pinfunction "0_0") (pintype "passive"))
      (node (ref "E104") (pin "0") (pinfunction "0_0") (pintype "passive"))
      (node (ref "E105") (pin "0") (pinfunction "0_0") (pintype "passive"))
      (node (ref "E106") (pin "0") (pinfunction "0_0") (pintype "passive"))
      (node (ref "E107") (pin "0") (pinfunction "0_0") (pintype "passive"))
      (node (ref "E108") (pin "0") (pinfunction "0_0") (pintype "passive"))
      (node (ref "E91") (pin "0") (pinfunction "0_0") (pintype "passive"))
      (node (ref "E92") (pin "0") (pinfunction "0_0") (pintype "passive"))
      (node (ref "E93") (pin "0") (pinfunction "0_0") (pintype "passive"))
      (node (ref "E94") (pin "0") (pinfunction "0_0") (pintype "passive"))
      (node (ref "E95") (pin "0") (pinfunction "0_0") (pintype "passive"))
      (node (ref "E96") (pin "0") (pinfunction "0_0") (pintype "passive"))
      (node (ref "E97") (pin "0") (pinfunction "0_0") (pintype "passive"))
      (node (ref "E98") (pin "0") (pinfunction "0_0") (pintype "passive"))
      (node (ref "E99") (pin "0") (pinfunction "0_0") (pintype "passive"))
    )
    (net (code "25") (name "/Row7") (class "Default")
      (node (ref "E109") (pin "0") (pinfunction "0_0") (pintype "passive"))
      (node (ref "E110") (pin "0") (pinfunction "0_0") (pintype "passive"))
      (node (ref "E111") (pin "0") (pinfunction "0_0") (pintype "passive"))
      (node (ref "E112") (pin "0") (pinfunction "0_0") (pintype "passive"))
      (node (ref "E113") (pin "0") (pinfunction "0_0") (pintype "passive"))
      (node (ref "E114") (pin "0") (pinfunction "0_0") (pintype "passive"))
      (node (ref "E115") (pin "0") (pinfunction "0_0") (pintype "passive"))
      (node (ref "E116") (pin "0") (pinfunction "0_0") (pintype "passive"))
      (node (ref "E117") (pin "0") (pinfunction "0_0") (pintype "passive"))
      (node (ref "E118") (pin "0") (pinfunction "0_0") (pintype "passive"))
      (node (ref "E119") (pin "0") (pinfunction "0_0") (pintype "passive"))
      (node (ref "E120") (pin "0") (pinfunction "0_0") (pintype "passive"))
      (node (ref "E121") (pin "0") (pinfunction "0_0") (pintype "passive"))
      (node (ref "E122") (pin "0") (pinfunction "0_0") (pintype "passive"))
      (node (ref "E123") (pin "0") (pinfunction "0_0") (pintype "passive"))
      (node (ref "E124") (pin "0") (pinfunction "0_0") (pintype "passive"))
      (node (ref "E125") (pin "0") (pinfunction "0_0") (pintype "passive"))
      (node (ref "E126") (pin "0") (pinfunction "0_0") (pintype "passive"))
    )
    (net (code "26") (name "/Row8") (class "Default")
      (node (ref "E127") (pin "0") (pinfunction "0_0") (pintype "passive"))
      (node (ref "E128") (pin "0") (pinfunction "0_0") (pintype "passive"))
      (node (ref "E129") (pin "0") (pinfunction "0_0") (pintype "passive"))
      (node (ref "E130") (pin "0") (pinfunction "0_0") (pintype "passive"))
      (node (ref "E131") (pin "0") (pinfunction "0_0") (pintype "passive"))
      (node (ref "E132") (pin "0") (pinfunction "0_0") (pintype "passive"))
      (node (ref "E133") (pin "0") (pinfunction "0_0") (pintype "passive"))
      (node (ref "E134") (pin "0") (pinfunction "0_0") (pintype "passive"))
      (node (ref "E135") (pin "0") (pinfunction "0_0") (pintype "passive"))
      (node (ref "E136") (pin "0") (pinfunction "0_0") (pintype "passive"))
      (node (ref "E137") (pin "0") (pinfunction "0_0") (pintype "passive"))
      (node (ref "E138") (pin "0") (pinfunction "0_0") (pintype "passive"))
      (node (ref "E139") (pin "0") (pinfunction "0_0") (pintype "passive"))
      (node (ref "E140") (pin "0") (pinfunction "0_0") (pintype "passive"))
      (node (ref "E141") (pin "0") (pinfunction "0_0") (pintype "passive"))
      (node (ref "E142") (pin "0") (pinfunction "0_0") (pintype "passive"))
      (node (ref "E143") (pin "0") (pinfunction "0_0") (pintype "passive"))
      (node (ref "E144") (pin "0") (pinfunction "0_0") (pintype "passive"))
    )
    (net (code "27") (name "/Row9") (class "Default")
      (node (ref "E145") (pin "0") (pinfunction "0_0") (pintype "passive"))
      (node (ref "E146") (pin "0") (pinfunction "0_0") (pintype "passive"))
      (node (ref "E147") (pin "0") (pinfunction "0_0") (pintype "passive"))
      (node (ref "E148") (pin "0") (pinfunction "0_0") (pintype "passive"))
      (node (ref "E149") (pin "0") (pinfunction "0_0") (pintype "passive"))
      (node (ref "E150") (pin "0") (pinfunction "0_0") (pintype "passive"))
      (node (ref "E151") (pin "0") (pinfunction "0_0") (pintype "passive"))
      (node (ref "E152") (pin "0") (pinfunction "0_0") (pintype "passive"))
      (node (ref "E153") (pin "0") (pinfunction "0_0") (pintype "passive"))
      (node (ref "E154") (pin "0") (pinfunction "0_0") (pintype "passive"))
      (node (ref "E155") (pin "0") (pinfunction "0_0") (pintype "passive"))
      (node (ref "E156") (pin "0") (pinfunction "0_0") (pintype "passive"))
      (node (ref "E157") (pin "0") (pinfunction "0_0") (pintype "passive"))
      (node (ref "E158") (pin "0") (pinfunction "0_0") (pintype "passive"))
      (node (ref "E159") (pin "0") (pinfunction "0_0") (pintype "passive"))
      (node (ref "E160") (pin "0") (pinfunction "0_0") (pintype "passive"))
      (node (ref "E161") (pin "0") (pinfunction "0_0") (pintype "passive"))
      (node (ref "E162") (pin "0") (pinfunction "0_0") (pintype "passive"))
    )
    (net (code "28") (name "/Row10") (class "Default")
      (node (ref "E163") (pin "0") (pinfunction "0_0") (pintype "passive"))
      (node (ref "E164") (pin "0") (pinfunction "0_0") (pintype "passive"))
      (node (ref "E165") (pin "0") (pinfunction "0_0") (pintype "passive"))
      (node (ref "E166") (pin "0") (pinfunction "0_0") (pintype "passive"))
      (node (ref "E167") (pin "0") (pinfunction "0_0") (pintype "passive"))
      (node (ref "E168") (pin "0") (pinfunction "0_0") (pintype "passive"))
      (node (ref "E169") (pin "0") (pinfunction "0_0") (pintype "passive"))
      (node (ref "E170") (pin "0") (pinfunction "0_0") (pintype "passive"))
      (node (ref "E171") (pin "0") (pinfunction "0_0") (pintype "passive"))
      (node (ref "E172") (pin "0") (pinfunction "0_0") (pintype "passive"))
      (node (ref "E173") (pin "0") (pinfunction "0_0") (pintype "passive"))
      (node (ref "E174") (pin "0") (pinfunction "0_0") (pintype "passive"))
      (node (ref "E175") (pin "0") (pinfunction "0_0") (pintype "passive"))
      (node (ref "E176") (pin "0") (pinfunction "0_0") (pintype "passive"))
      (node (ref "E177") (pin "0") (pinfunction "0_0") (pintype "passive"))
      (node (ref "E178") (pin "0") (pinfunction "0_0") (pintype "passive"))
      (node (ref "E179") (pin "0") (pinfunction "0_0") (pintype "passive"))
      (node (ref "E180") (pin "0") (pinfunction "0_0") (pintype "passive"))
    )
    (net (code "29") (name "/Row11") (class "Default")
      (node (ref "E181") (pin "0") (pinfunction "0_0") (pintype "passive"))
      (node (ref "E182") (pin "0") (pinfunction "0_0") (pintype "passive"))
      (node (ref "E183") (pin "0") (pinfunction "0_0") (pintype "passive"))
      (node (ref "E184") (pin "0") (pinfunction "0_0") (pintype "passive"))
      (node (ref "E185") (pin "0") (pinfunction "0_0") (pintype "passive"))
      (node (ref "E186") (pin "0") (pinfunction "0_0") (pintype "passive"))
      (node (ref "E187") (pin "0") (pinfunction "0_0") (pintype "passive"))
      (node (ref "E188") (pin "0") (pinfunction "0_0") (pintype "passive"))
      (node (ref "E189") (pin "0") (pinfunction "0_0") (pintype "passive"))
      (node (ref "E190") (pin "0") (pinfunction "0_0") (pintype "passive"))
      (node (ref "E191") (pin "0") (pinfunction "0_0") (pintype "passive"))
      (node (ref "E192") (pin "0") (pinfunction "0_0") (pintype "passive"))
      (node (ref "E193") (pin "0") (pinfunction "0_0") (pintype "passive"))
      (node (ref "E194") (pin "0") (pinfunction "0_0") (pintype "passive"))
      (node (ref "E195") (pin "0") (pinfunction "0_0") (pintype "passive"))
      (node (ref "E196") (pin "0") (pinfunction "0_0") (pintype "passive"))
      (node (ref "E197") (pin "0") (pinfunction "0_0") (pintype "passive"))
      (node (ref "E198") (pin "0") (pinfunction "0_0") (pintype "passive"))
    )
    (net (code "30") (name "/Row12") (class "Default")
      (node (ref "E199") (pin "0") (pinfunction "0_0") (pintype "passive"))
      (node (ref "E200") (pin "0") (pinfunction "0_0") (pintype "passive"))
      (node (ref "E201") (pin "0") (pinfunction "0_0") (pintype "passive"))
      (node (ref "E202") (pin "0") (pinfunction "0_0") (pintype "passive"))
      (node (ref "E203") (pin "0") (pinfunction "0_0") (pintype "passive"))
      (node (ref "E204") (pin "0") (pinfunction "0_0") (pintype "passive"))
      (node (ref "E205") (pin "0") (pinfunction "0_0") (pintype "passive"))
      (node (ref "E206") (pin "0") (pinfunction "0_0") (pintype "passive"))
      (node (ref "E207") (pin "0") (pinfunction "0_0") (pintype "passive"))
      (node (ref "E208") (pin "0") (pinfunction "0_0") (pintype "passive"))
      (node (ref "E209") (pin "0") (pinfunction "0_0") (pintype "passive"))
      (node (ref "E210") (pin "0") (pinfunction "0_0") (pintype "passive"))
      (node (ref "E211") (pin "0") (pinfunction "0_0") (pintype "passive"))
      (node (ref "E212") (pin "0") (pinfunction "0_0") (pintype "passive"))
      (node (ref "E213") (pin "0") (pinfunction "0_0") (pintype "passive"))
      (node (ref "E214") (pin "0") (pinfunction "0_0") (pintype "passive"))
      (node (ref "E215") (pin "0") (pinfunction "0_0") (pintype "passive"))
      (node (ref "E216") (pin "0") (pinfunction "0_0") (pintype "passive"))
    )
    (net (code "31") (name "/Row13") (class "Default")
      (node (ref "E217") (pin "0") (pinfunction "0_0") (pintype "passive"))
      (node (ref "E218") (pin "0") (pinfunction "0_0") (pintype "passive"))
      (node (ref "E219") (pin "0") (pinfunction "0_0") (pintype "passive"))
      (node (ref "E220") (pin "0") (pinfunction "0_0") (pintype "passive"))
      (node (ref "E221") (pin "0") (pinfunction "0_0") (pintype "passive"))
      (node (ref "E222") (pin "0") (pinfunction "0_0") (pintype "passive"))
      (node (ref "E223") (pin "0") (pinfunction "0_0") (pintype "passive"))
      (node (ref "E224") (pin "0") (pinfunction "0_0") (pintype "passive"))
      (node (ref "E225") (pin "0") (pinfunction "0_0") (pintype "passive"))
      (node (ref "E226") (pin "0") (pinfunction "0_0") (pintype "passive"))
      (node (ref "E227") (pin "0") (pinfunction "0_0") (pintype "passive"))
      (node (ref "E228") (pin "0") (pinfunction "0_0") (pintype "passive"))
      (node (ref "E229") (pin "0") (pinfunction "0_0") (pintype "passive"))
      (node (ref "E230") (pin "0") (pinfunction "0_0") (pintype "passive"))
      (node (ref "E231") (pin "0") (pinfunction "0_0") (pintype "passive"))
      (node (ref "E232") (pin "0") (pinfunction "0_0") (pintype "passive"))
      (node (ref "E233") (pin "0") (pinfunction "0_0") (pintype "passive"))
      (node (ref "E234") (pin "0") (pinfunction "0_0") (pintype "passive"))
    )
    (net (code "32") (name "/Row14") (class "Default")
      (node (ref "E235") (pin "0") (pinfunction "0_0") (pintype "passive"))
      (node (ref "E236") (pin "0") (pinfunction "0_0") (pintype "passive"))
      (node (ref "E237") (pin "0") (pinfunction "0_0") (pintype "passive"))
      (node (ref "E238") (pin "0") (pinfunction "0_0") (pintype "passive"))
      (node (ref "E239") (pin "0") (pinfunction "0_0") (pintype "passive"))
      (node (ref "E240") (pin "0") (pinfunction "0_0") (pintype "passive"))
      (node (ref "E241") (pin "0") (pinfunction "0_0") (pintype "passive"))
      (node (ref "E242") (pin "0") (pinfunction "0_0") (pintype "passive"))
      (node (ref "E243") (pin "0") (pinfunction "0_0") (pintype "passive"))
      (node (ref "E244") (pin "0") (pinfunction "0_0") (pintype "passive"))
      (node (ref "E245") (pin "0") (pinfunction "0_0") (pintype "passive"))
      (node (ref "E246") (pin "0") (pinfunction "0_0") (pintype "passive"))
      (node (ref "E247") (pin "0") (pinfunction "0_0") (pintype "passive"))
      (node (ref "E248") (pin "0") (pinfunction "0_0") (pintype "passive"))
      (node (ref "E249") (pin "0") (pinfunction "0_0") (pintype "passive"))
      (node (ref "E250") (pin "0") (pinfunction "0_0") (pintype "passive"))
      (node (ref "E251") (pin "0") (pinfunction "0_0") (pintype "passive"))
      (node (ref "E252") (pin "0") (pinfunction "0_0") (pintype "passive"))
    )
    (net (code "33") (name "/Row15") (class "Default")
      (node (ref "E253") (pin "0") (pinfunction "0_0") (pintype "passive"))
      (node (ref "E254") (pin "0") (pinfunction "0_0") (pintype "passive"))
      (node (ref "E255") (pin "0") (pinfunction "0_0") (pintype "passive"))
      (node (ref "E256") (pin "0") (pinfunction "0_0") (pintype "passive"))
      (node (ref "E257") (pin "0") (pinfunction "0_0") (pintype "passive"))
      (node (ref "E258") (pin "0") (pinfunction "0_0") (pintype "passive"))
      (node (ref "E259") (pin "0") (pinfunction "0_0") (pintype "passive"))
      (node (ref "E260") (pin "0") (pinfunction "0_0") (pintype "passive"))
      (node (ref "E261") (pin "0") (pinfunction "0_0") (pintype "passive"))
      (node (ref "E262") (pin "0") (pinfunction "0_0") (pintype "passive"))
      (node (ref "E263") (pin "0") (pinfunction "0_0") (pintype "passive"))
      (node (ref "E264") (pin "0") (pinfunction "0_0") (pintype "passive"))
      (node (ref "E265") (pin "0") (pinfunction "0_0") (pintype "passive"))
      (node (ref "E266") (pin "0") (pinfunction "0_0") (pintype "passive"))
      (node (ref "E267") (pin "0") (pinfunction "0_0") (pintype "passive"))
      (node (ref "E268") (pin "0") (pinfunction "0_0") (pintype "passive"))
      (node (ref "E269") (pin "0") (pinfunction "0_0") (pintype "passive"))
      (node (ref "E270") (pin "0") (pinfunction "0_0") (pintype "passive"))
    )
    (net (code "34") (name "/Row16") (class "Default")
      (node (ref "E271") (pin "0") (pinfunction "0_0") (pintype "passive"))
      (node (ref "E272") (pin "0") (pinfunction "0_0") (pintype "passive"))
      (node (ref "E273") (pin "0") (pinfunction "0_0") (pintype "passive"))
      (node (ref "E274") (pin "0") (pinfunction "0_0") (pintype "passive"))
      (node (ref "E275") (pin "0") (pinfunction "0_0") (pintype "passive"))
      (node (ref "E276") (pin "0") (pinfunction "0_0") (pintype "passive"))
      (node (ref "E277") (pin "0") (pinfunction "0_0") (pintype "passive"))
      (node (ref "E278") (pin "0") (pinfunction "0_0") (pintype "passive"))
      (node (ref "E279") (pin "0") (pinfunction "0_0") (pintype "passive"))
      (node (ref "E280") (pin "0") (pinfunction "0_0") (pintype "passive"))
      (node (ref "E281") (pin "0") (pinfunction "0_0") (pintype "passive"))
      (node (ref "E282") (pin "0") (pinfunction "0_0") (pintype "passive"))
      (node (ref "E283") (pin "0") (pinfunction "0_0") (pintype "passive"))
      (node (ref "E284") (pin "0") (pinfunction "0_0") (pintype "passive"))
      (node (ref "E285") (pin "0") (pinfunction "0_0") (pintype "passive"))
      (node (ref "E286") (pin "0") (pinfunction "0_0") (pintype "passive"))
      (node (ref "E287") (pin "0") (pinfunction "0_0") (pintype "passive"))
      (node (ref "E288") (pin "0") (pinfunction "0_0") (pintype "passive"))
      (node (ref "E289") (pin "0") (pinfunction "0_0") (pintype "passive"))
      (node (ref "E290") (pin "0") (pinfunction "0_0") (pintype "passive"))
      (node (ref "E291") (pin "0") (pinfunction "0_0") (pintype "passive"))
      (node (ref "E292") (pin "0") (pinfunction "0_0") (pintype "passive"))
      (node (ref "E293") (pin "0") (pinfunction "0_0") (pintype "passive"))
      (node (ref "E294") (pin "0") (pinfunction "0_0") (pintype "passive"))
      (node (ref "E295") (pin "0") (pinfunction "0_0") (pintype "passive"))
      (node (ref "E296") (pin "0") (pinfunction "0_0") (pintype "passive"))
      (node (ref "E297") (pin "0") (pinfunction "0_0") (pintype "passive"))
      (node (ref "E298") (pin "0") (pinfunction "0_0") (pintype "passive"))
      (node (ref "E299") (pin "0") (pinfunction "0_0") (pintype "passive"))
      (node (ref "E300") (pin "0") (pinfunction "0_0") (pintype "passive"))
      (node (ref "E301") (pin "0") (pinfunction "0_0") (pintype "passive"))
      (node (ref "E302") (pin "0") (pinfunction "0_0") (pintype "passive"))
      (node (ref "E303") (pin "0") (pinfunction "0_0") (pintype "passive"))
      (node (ref "E304") (pin "0") (pinfunction "0_0") (pintype "passive"))
      (node (ref "E305") (pin "0") (pinfunction "0_0") (pintype "passive"))
      (node (ref "E306") (pin "0") (pinfunction "0_0") (pintype "passive"))
      (node (ref "E307") (pin "0") (pinfunction "0_0") (pintype "passive"))
      (node (ref "E308") (pin "0") (pinfunction "0_0") (pintype "passive"))
      (node (ref "E309") (pin "0") (pinfunction "0_0") (pintype "passive"))
      (node (ref "E310") (pin "0") (pinfunction "0_0") (pintype "passive"))
      (node (ref "E311") (pin "0") (pinfunction "0_0") (pintype "passive"))
      (node (ref "E312") (pin "0") (pinfunction "0_0") (pintype "passive"))
      (node (ref "E313") (pin "0") (pinfunction "0_0") (pintype "passive"))
      (node (ref "E314") (pin "0") (pinfunction "0_0") (pintype "passive"))
      (node (ref "E315") (pin "0") (pinfunction "0_0") (pintype "passive"))
      (node (ref "E316") (pin "0") (pinfunction "0_0") (pintype "passive"))
      (node (ref "E317") (pin "0") (pinfunction "0_0") (pintype "passive"))
      (node (ref "E318") (pin "0") (pinfunction "0_0") (pintype "passive"))
      (node (ref "E319") (pin "0") (pinfunction "0_0") (pintype "passive"))
      (node (ref "E320") (pin "0") (pinfunction "0_0") (pintype "passive"))
      (node (ref "E321") (pin "0") (pinfunction "0_0") (pintype "passive"))
      (node (ref "E322") (pin "0") (pinfunction "0_0") (pintype "passive"))
      (node (ref "E323") (pin "0") (pinfunction "0_0") (pintype "passive"))
      (node (ref "E324") (pin "0") (pinfunction "0_0") (pintype "passive"))
    )
  )
)
